# PCB_-_nrf52840.net
KiCad netlist of a schematic drawn in EAGLE
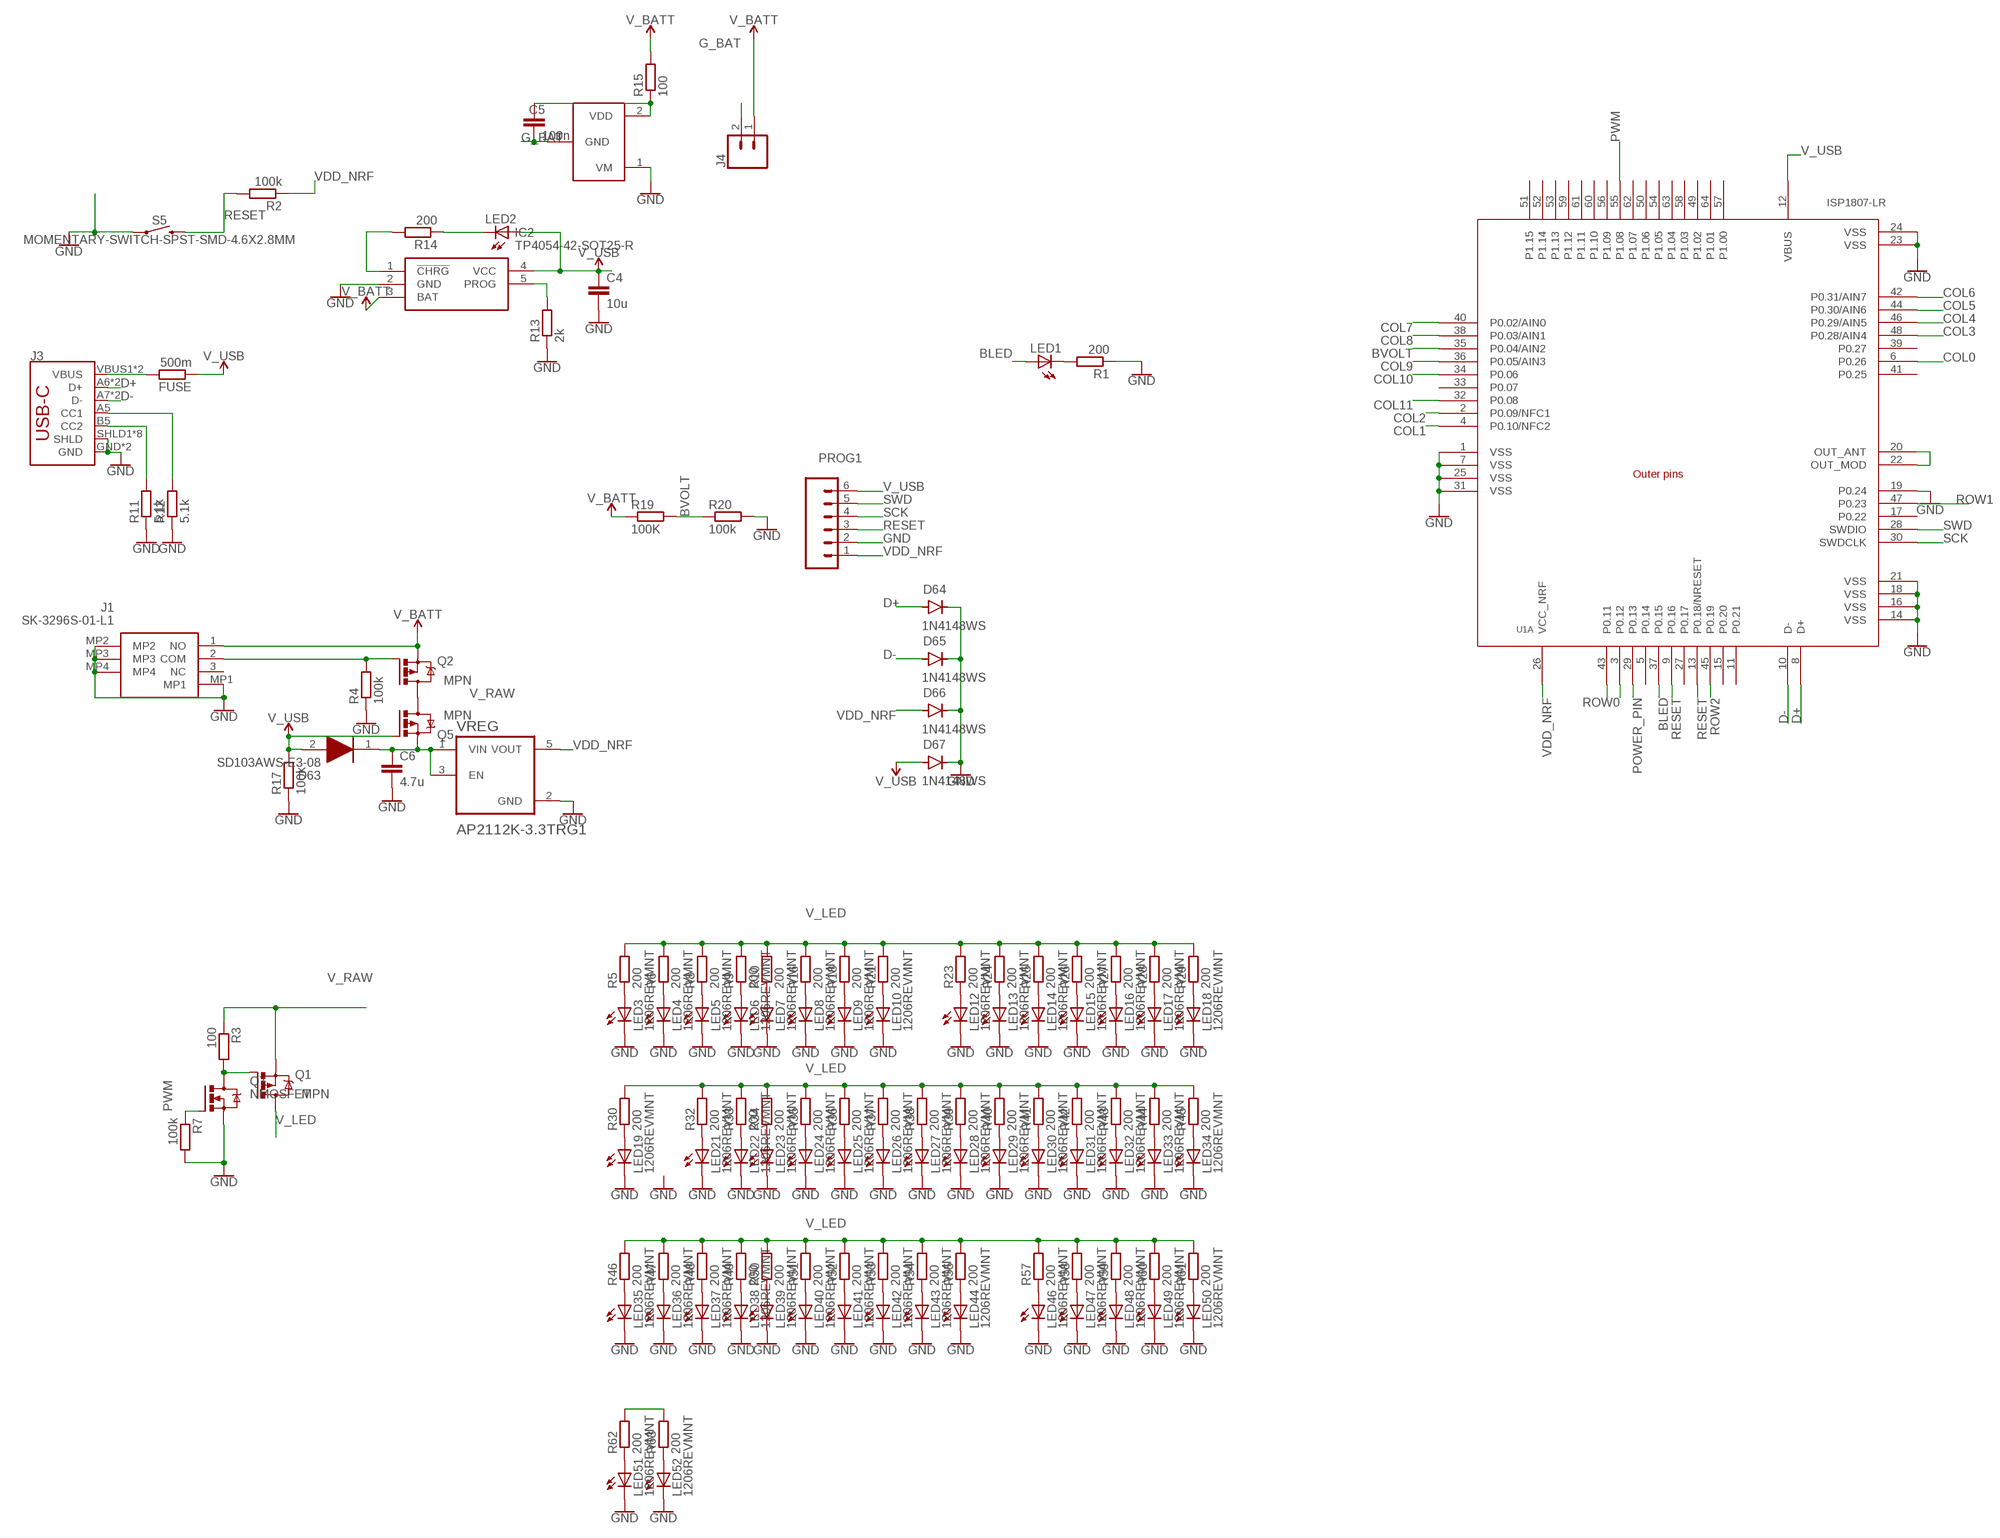
[diagram p0: schematic, sheet 1, part 1 of 2]
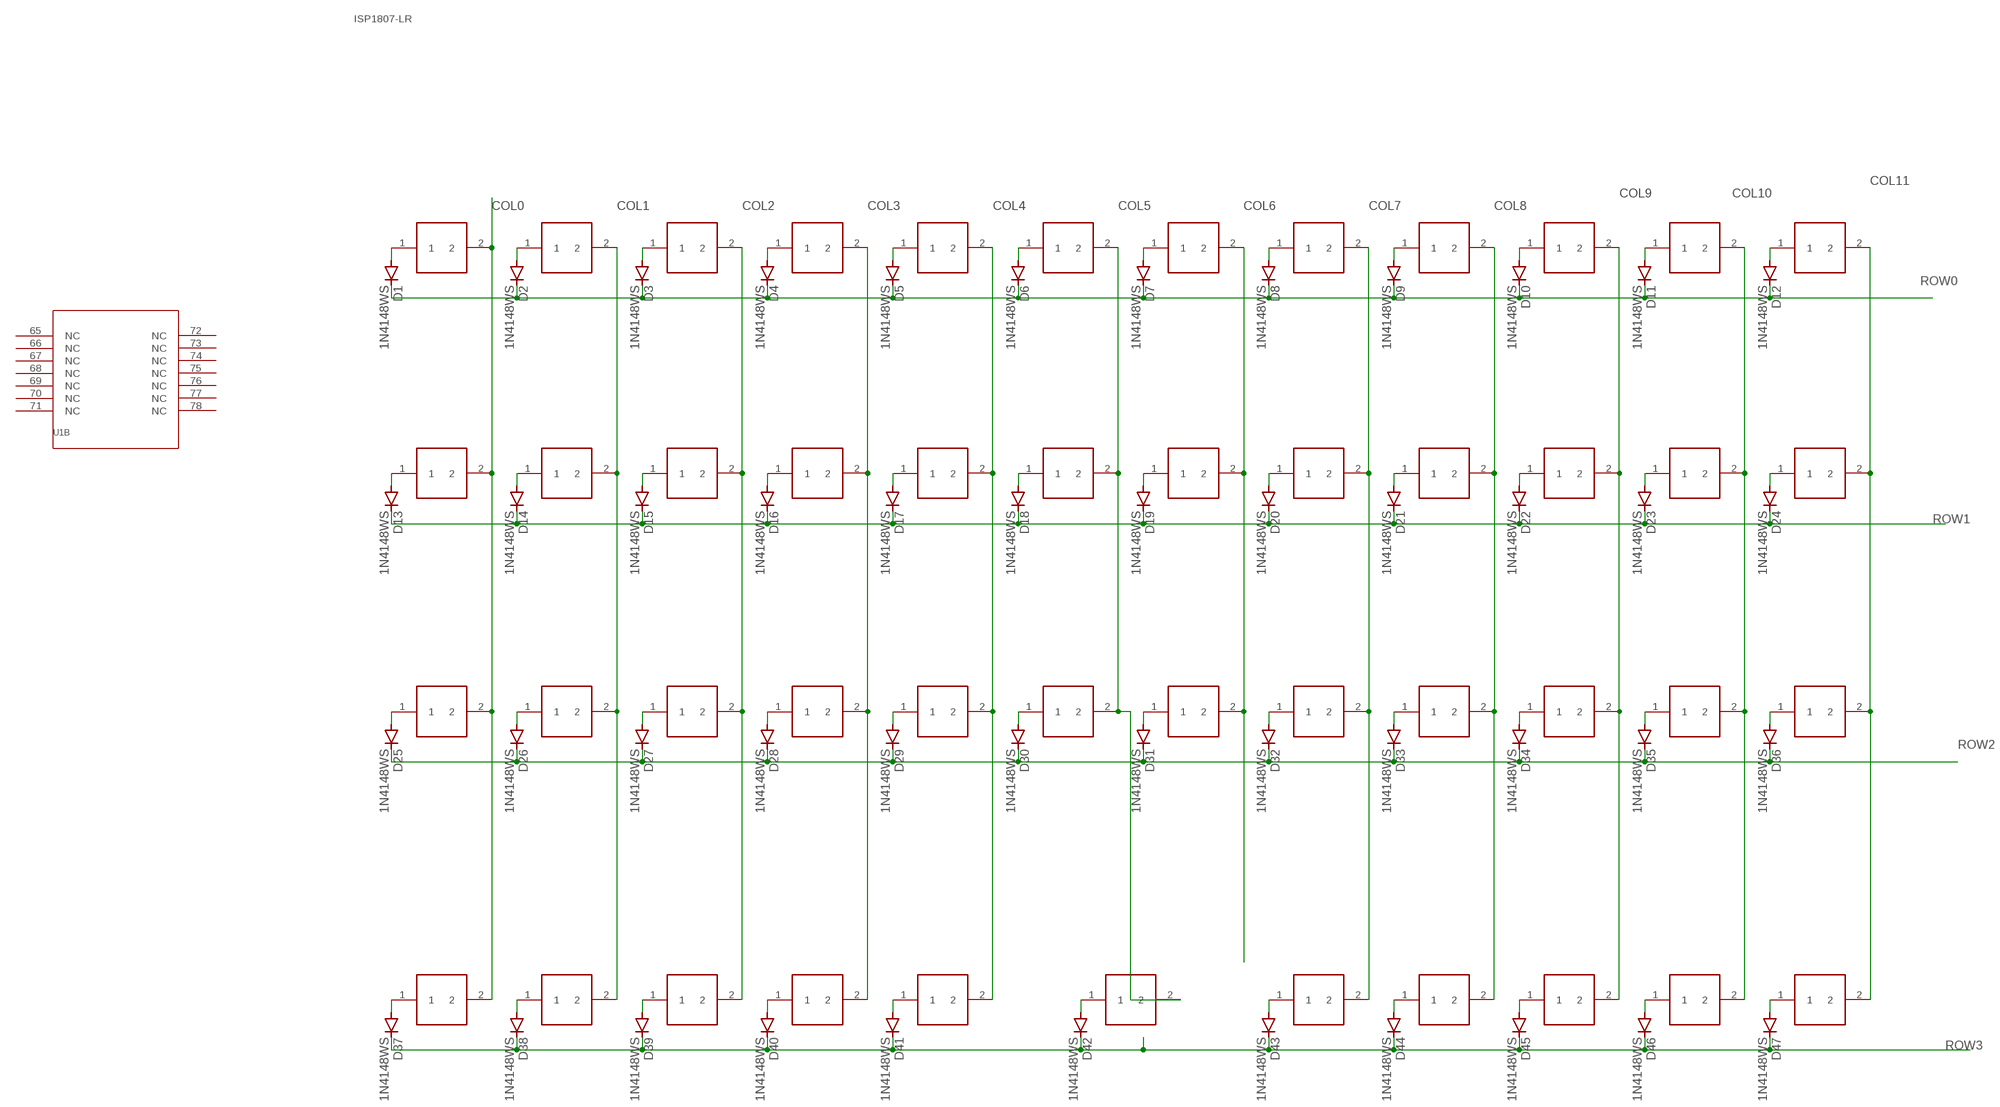
[diagram p1: schematic, sheet 1, part 2 of 2]

(export (version "E")
  (design (tool "Eeschema 10.0.6"))
  (components
    (comp (ref "5")
      (value "CHERRYLOWPRO")
      (footprint "eagle-import:CHERRY-LOWPRO")
      (libsource (lib "eagle-import") (part "CHERRYLOWPRO"))
    )
    (comp (ref "6")
      (value "CHERRYLOWPRO")
      (footprint "eagle-import:CHERRY-LOWPRO")
      (libsource (lib "eagle-import") (part "CHERRYLOWPRO"))
    )
    (comp (ref "7")
      (value "CHERRYLOWPRO")
      (footprint "eagle-import:CHERRY-LOWPRO")
      (libsource (lib "eagle-import") (part "CHERRYLOWPRO"))
    )
    (comp (ref "8")
      (value "CHERRYLOWPRO")
      (footprint "eagle-import:CHERRY-LOWPRO")
      (libsource (lib "eagle-import") (part "CHERRYLOWPRO"))
    )
    (comp (ref "12")
      (value "CHERRYLOWPRO")
      (footprint "eagle-import:CHERRY-LOWPRO")
      (libsource (lib "eagle-import") (part "CHERRYLOWPRO"))
    )
    (comp (ref "13")
      (value "CHERRYLOWPRO")
      (footprint "eagle-import:CHERRY-LOWPRO")
      (libsource (lib "eagle-import") (part "CHERRYLOWPRO"))
    )
    (comp (ref "14")
      (value "CHERRYLOWPRO")
      (footprint "eagle-import:CHERRY-LOWPRO")
      (libsource (lib "eagle-import") (part "CHERRYLOWPRO"))
    )
    (comp (ref "15")
      (value "CHERRYLOWPRO")
      (footprint "eagle-import:CHERRY-LOWPRO")
      (libsource (lib "eagle-import") (part "CHERRYLOWPRO"))
    )
    (comp (ref "16")
      (value "CHERRYLOWPRO")
      (footprint "eagle-import:CHERRY-LOWPRO")
      (libsource (lib "eagle-import") (part "CHERRYLOWPRO"))
    )
    (comp (ref "17")
      (value "CHERRYLOWPRO")
      (footprint "eagle-import:CHERRY-LOWPRO")
      (libsource (lib "eagle-import") (part "CHERRYLOWPRO"))
    )
    (comp (ref "18")
      (value "CHERRYLOWPRO")
      (footprint "eagle-import:CHERRY-LOWPRO")
      (libsource (lib "eagle-import") (part "CHERRYLOWPRO"))
    )
    (comp (ref "19")
      (value "CHERRYLOWPRO")
      (footprint "eagle-import:CHERRY-LOWPRO")
      (libsource (lib "eagle-import") (part "CHERRYLOWPRO"))
    )
    (comp (ref "21")
      (value "CHERRYLOWPRO")
      (footprint "eagle-import:CHERRY-LOWPRO")
      (libsource (lib "eagle-import") (part "CHERRYLOWPRO"))
    )
    (comp (ref "22")
      (value "CHERRYLOWPRO")
      (footprint "eagle-import:CHERRY-LOWPRO")
      (libsource (lib "eagle-import") (part "CHERRYLOWPRO"))
    )
    (comp (ref "23")
      (value "CHERRYLOWPRO")
      (footprint "eagle-import:CHERRY-LOWPRO")
      (libsource (lib "eagle-import") (part "CHERRYLOWPRO"))
    )
    (comp (ref "24")
      (value "CHERRYLOWPRO")
      (footprint "eagle-import:CHERRY-LOWPRO")
      (libsource (lib "eagle-import") (part "CHERRYLOWPRO"))
    )
    (comp (ref "25")
      (value "CHERRYLOWPRO")
      (footprint "eagle-import:CHERRY-LOWPRO")
      (libsource (lib "eagle-import") (part "CHERRYLOWPRO"))
    )
    (comp (ref "26")
      (value "CHERRYLOWPRO")
      (footprint "eagle-import:CHERRY-LOWPRO")
      (libsource (lib "eagle-import") (part "CHERRYLOWPRO"))
    )
    (comp (ref "27")
      (value "CHERRYLOWPRO")
      (footprint "eagle-import:CHERRY-LOWPRO")
      (libsource (lib "eagle-import") (part "CHERRYLOWPRO"))
    )
    (comp (ref "28")
      (value "CHERRYLOWPRO")
      (footprint "eagle-import:CHERRY-LOWPRO")
      (libsource (lib "eagle-import") (part "CHERRYLOWPRO"))
    )
    (comp (ref "29")
      (value "CHERRYLOWPRO")
      (footprint "eagle-import:CHERRY-LOWPRO")
      (libsource (lib "eagle-import") (part "CHERRYLOWPRO"))
    )
    (comp (ref "31")
      (value "CHERRYLOWPRO")
      (footprint "eagle-import:CHERRY-LOWPRO")
      (libsource (lib "eagle-import") (part "CHERRYLOWPRO"))
    )
    (comp (ref "32")
      (value "CHERRYLOWPRO")
      (footprint "eagle-import:CHERRY-LOWPRO")
      (libsource (lib "eagle-import") (part "CHERRYLOWPRO"))
    )
    (comp (ref "33")
      (value "CHERRYLOWPRO")
      (footprint "eagle-import:CHERRY-LOWPRO")
      (libsource (lib "eagle-import") (part "CHERRYLOWPRO"))
    )
    (comp (ref "34")
      (value "CHERRYLOWPRO")
      (footprint "eagle-import:CHERRY-LOWPRO")
      (libsource (lib "eagle-import") (part "CHERRYLOWPRO"))
    )
    (comp (ref "35")
      (value "CHERRYLOWPRO")
      (footprint "eagle-import:CHERRY-LOWPRO")
      (libsource (lib "eagle-import") (part "CHERRYLOWPRO"))
    )
    (comp (ref "36")
      (value "CHERRYLOWPRO")
      (footprint "eagle-import:CHERRY-LOWPRO")
      (libsource (lib "eagle-import") (part "CHERRYLOWPRO"))
    )
    (comp (ref "37")
      (value "CHERRYLOWPRO")
      (footprint "eagle-import:CHERRY-LOWPRO")
      (libsource (lib "eagle-import") (part "CHERRYLOWPRO"))
    )
    (comp (ref "38")
      (value "CHERRYLOWPRO")
      (footprint "eagle-import:CHERRY-LOWPRO")
      (libsource (lib "eagle-import") (part "CHERRYLOWPRO"))
    )
    (comp (ref "39")
      (value "CHERRYLOWPRO")
      (footprint "eagle-import:CHERRY-LOWPRO")
      (libsource (lib "eagle-import") (part "CHERRYLOWPRO"))
    )
    (comp (ref "42")
      (value "CHERRYLOWPRO")
      (footprint "eagle-import:CHERRY-LOWPRO")
      (libsource (lib "eagle-import") (part "CHERRYLOWPRO"))
    )
    (comp (ref "43")
      (value "CHERRYLOWPRO")
      (footprint "eagle-import:CHERRY-LOWPRO")
      (libsource (lib "eagle-import") (part "CHERRYLOWPRO"))
    )
    (comp (ref "44")
      (value "CHERRYLOWPRO")
      (footprint "eagle-import:CHERRY-LOWPRO")
      (libsource (lib "eagle-import") (part "CHERRYLOWPRO"))
    )
    (comp (ref "45")
      (value "CHERRYLOWPRO")
      (footprint "eagle-import:CHERRY-LOWPRO")
      (libsource (lib "eagle-import") (part "CHERRYLOWPRO"))
    )
    (comp (ref "46")
      (value "CHERRYLOWPRO")
      (footprint "eagle-import:CHERRY-LOWPRO")
      (libsource (lib "eagle-import") (part "CHERRYLOWPRO"))
    )
    (comp (ref "47")
      (value "CHERRYLOWPRO")
      (footprint "eagle-import:CHERRY-LOWPRO")
      (libsource (lib "eagle-import") (part "CHERRYLOWPRO"))
    )
    (comp (ref "48")
      (value "CHERRYLOWPRO")
      (footprint "eagle-import:CHERRY-LOWPRO")
      (libsource (lib "eagle-import") (part "CHERRYLOWPRO"))
    )
    (comp (ref "49")
      (value "CHERRYLOWPRO")
      (footprint "eagle-import:CHERRY-LOWPRO")
      (libsource (lib "eagle-import") (part "CHERRYLOWPRO"))
    )
    (comp (ref "110")
      (value "CHERRYLOWPRO")
      (footprint "eagle-import:CHERRY-LOWPRO")
      (libsource (lib "eagle-import") (part "CHERRYLOWPRO"))
    )
    (comp (ref "111")
      (value "CHERRYLOWPRO")
      (footprint "eagle-import:CHERRY-LOWPRO")
      (libsource (lib "eagle-import") (part "CHERRYLOWPRO"))
    )
    (comp (ref "210")
      (value "CHERRYLOWPRO")
      (footprint "eagle-import:CHERRY-LOWPRO")
      (libsource (lib "eagle-import") (part "CHERRYLOWPRO"))
    )
    (comp (ref "211")
      (value "CHERRYLOWPRO")
      (footprint "eagle-import:CHERRY-LOWPRO")
      (libsource (lib "eagle-import") (part "CHERRYLOWPRO"))
    )
    (comp (ref "212")
      (value "CHERRYLOWPRO")
      (footprint "eagle-import:CHERRY-LOWPRO")
      (libsource (lib "eagle-import") (part "CHERRYLOWPRO"))
    )
    (comp (ref "310")
      (value "CHERRYLOWPRO")
      (footprint "eagle-import:CHERRY-LOWPRO")
      (libsource (lib "eagle-import") (part "CHERRYLOWPRO"))
    )
    (comp (ref "311")
      (value "CHERRYLOWPRO")
      (footprint "eagle-import:CHERRY-LOWPRO")
      (libsource (lib "eagle-import") (part "CHERRYLOWPRO"))
    )
    (comp (ref "312")
      (value "CHERRYLOWPRO")
      (footprint "eagle-import:CHERRY-LOWPRO")
      (libsource (lib "eagle-import") (part "CHERRYLOWPRO"))
    )
    (comp (ref "410")
      (value "CHERRYLOWPRO")
      (footprint "eagle-import:CHERRY-LOWPRO")
      (libsource (lib "eagle-import") (part "CHERRYLOWPRO"))
    )
    (comp (ref "C4")
      (value "10u")
      (footprint "eagle-import:C0603")
      (libsource (lib "eagle-import") (part "resistor_348_C-EUC0603"))
    )
    (comp (ref "C5")
      (value "100n")
      (footprint "eagle-import:C0603")
      (libsource (lib "eagle-import") (part "resistor_348_C-EUC0603"))
    )
    (comp (ref "C6")
      (value "4.7u")
      (footprint "eagle-import:C0603")
      (libsource (lib "eagle-import") (part "C-EUC0603"))
    )
    (comp (ref "D1")
      (value "1N4148WS")
      (footprint "eagle-import:SOD-323")
      (fields
        (field (name "DIGIKEY_PART_NUMBER") "1N4148WSFSTR-ND")
        (field (name "MANUFACTURER") "Diodes Incorporated")
        (field (name "CREATED_BY") "PCBLayout.com")
      )
      (libsource (lib "eagle-import") (part "Volume_V1_32198814_1N4148WS"))
    )
    (comp (ref "D2")
      (value "1N4148WS")
      (footprint "eagle-import:SOD-323")
      (fields
        (field (name "DIGIKEY_PART_NUMBER") "1N4148WSFSTR-ND")
        (field (name "MANUFACTURER") "Diodes Incorporated")
        (field (name "CREATED_BY") "PCBLayout.com")
      )
      (libsource (lib "eagle-import") (part "Volume_V1_32198814_1N4148WS"))
    )
    (comp (ref "D3")
      (value "1N4148WS")
      (footprint "eagle-import:SOD-323")
      (fields
        (field (name "DIGIKEY_PART_NUMBER") "1N4148WSFSTR-ND")
        (field (name "MANUFACTURER") "Diodes Incorporated")
        (field (name "CREATED_BY") "PCBLayout.com")
      )
      (libsource (lib "eagle-import") (part "Volume_V1_32198814_1N4148WS"))
    )
    (comp (ref "D4")
      (value "1N4148WS")
      (footprint "eagle-import:SOD-323")
      (fields
        (field (name "DIGIKEY_PART_NUMBER") "1N4148WSFSTR-ND")
        (field (name "MANUFACTURER") "Diodes Incorporated")
        (field (name "CREATED_BY") "PCBLayout.com")
      )
      (libsource (lib "eagle-import") (part "Volume_V1_32198814_1N4148WS"))
    )
    (comp (ref "D5")
      (value "1N4148WS")
      (footprint "eagle-import:SOD-323")
      (fields
        (field (name "DIGIKEY_PART_NUMBER") "1N4148WSFSTR-ND")
        (field (name "MANUFACTURER") "Diodes Incorporated")
        (field (name "CREATED_BY") "PCBLayout.com")
      )
      (libsource (lib "eagle-import") (part "Volume_V1_32198814_1N4148WS"))
    )
    (comp (ref "D6")
      (value "1N4148WS")
      (footprint "eagle-import:SOD-323")
      (fields
        (field (name "DIGIKEY_PART_NUMBER") "1N4148WSFSTR-ND")
        (field (name "MANUFACTURER") "Diodes Incorporated")
        (field (name "CREATED_BY") "PCBLayout.com")
      )
      (libsource (lib "eagle-import") (part "Volume_V1_32198814_1N4148WS"))
    )
    (comp (ref "D7")
      (value "1N4148WS")
      (footprint "eagle-import:SOD-323")
      (fields
        (field (name "DIGIKEY_PART_NUMBER") "1N4148WSFSTR-ND")
        (field (name "MANUFACTURER") "Diodes Incorporated")
        (field (name "CREATED_BY") "PCBLayout.com")
      )
      (libsource (lib "eagle-import") (part "Volume_V1_32198814_1N4148WS"))
    )
    (comp (ref "D8")
      (value "1N4148WS")
      (footprint "eagle-import:SOD-323")
      (fields
        (field (name "DIGIKEY_PART_NUMBER") "1N4148WSFSTR-ND")
        (field (name "MANUFACTURER") "Diodes Incorporated")
        (field (name "CREATED_BY") "PCBLayout.com")
      )
      (libsource (lib "eagle-import") (part "Volume_V1_32198814_1N4148WS"))
    )
    (comp (ref "D9")
      (value "1N4148WS")
      (footprint "eagle-import:SOD-323")
      (fields
        (field (name "DIGIKEY_PART_NUMBER") "1N4148WSFSTR-ND")
        (field (name "MANUFACTURER") "Diodes Incorporated")
        (field (name "CREATED_BY") "PCBLayout.com")
      )
      (libsource (lib "eagle-import") (part "Volume_V1_32198814_1N4148WS"))
    )
    (comp (ref "D10")
      (value "1N4148WS")
      (footprint "eagle-import:SOD-323")
      (fields
        (field (name "DIGIKEY_PART_NUMBER") "1N4148WSFSTR-ND")
        (field (name "MANUFACTURER") "Diodes Incorporated")
        (field (name "CREATED_BY") "PCBLayout.com")
      )
      (libsource (lib "eagle-import") (part "Volume_V1_32198814_1N4148WS"))
    )
    (comp (ref "D11")
      (value "1N4148WS")
      (footprint "eagle-import:SOD-323")
      (fields
        (field (name "DIGIKEY_PART_NUMBER") "1N4148WSFSTR-ND")
        (field (name "MANUFACTURER") "Diodes Incorporated")
        (field (name "CREATED_BY") "PCBLayout.com")
      )
      (libsource (lib "eagle-import") (part "Volume_V1_32198814_1N4148WS"))
    )
    (comp (ref "D12")
      (value "1N4148WS")
      (footprint "eagle-import:SOD-323")
      (fields
        (field (name "DIGIKEY_PART_NUMBER") "1N4148WSFSTR-ND")
        (field (name "MANUFACTURER") "Diodes Incorporated")
        (field (name "CREATED_BY") "PCBLayout.com")
      )
      (libsource (lib "eagle-import") (part "Volume_V1_32198814_1N4148WS"))
    )
    (comp (ref "D13")
      (value "1N4148WS")
      (footprint "eagle-import:SOD-323")
      (fields
        (field (name "DIGIKEY_PART_NUMBER") "1N4148WSFSTR-ND")
        (field (name "MANUFACTURER") "Diodes Incorporated")
        (field (name "CREATED_BY") "PCBLayout.com")
      )
      (libsource (lib "eagle-import") (part "Volume_V1_32198814_1N4148WS"))
    )
    (comp (ref "D14")
      (value "1N4148WS")
      (footprint "eagle-import:SOD-323")
      (fields
        (field (name "DIGIKEY_PART_NUMBER") "1N4148WSFSTR-ND")
        (field (name "MANUFACTURER") "Diodes Incorporated")
        (field (name "CREATED_BY") "PCBLayout.com")
      )
      (libsource (lib "eagle-import") (part "Volume_V1_32198814_1N4148WS"))
    )
    (comp (ref "D15")
      (value "1N4148WS")
      (footprint "eagle-import:SOD-323")
      (fields
        (field (name "DIGIKEY_PART_NUMBER") "1N4148WSFSTR-ND")
        (field (name "MANUFACTURER") "Diodes Incorporated")
        (field (name "CREATED_BY") "PCBLayout.com")
      )
      (libsource (lib "eagle-import") (part "Volume_V1_32198814_1N4148WS"))
    )
    (comp (ref "D16")
      (value "1N4148WS")
      (footprint "eagle-import:SOD-323")
      (fields
        (field (name "DIGIKEY_PART_NUMBER") "1N4148WSFSTR-ND")
        (field (name "MANUFACTURER") "Diodes Incorporated")
        (field (name "CREATED_BY") "PCBLayout.com")
      )
      (libsource (lib "eagle-import") (part "Volume_V1_32198814_1N4148WS"))
    )
    (comp (ref "D17")
      (value "1N4148WS")
      (footprint "eagle-import:SOD-323")
      (fields
        (field (name "DIGIKEY_PART_NUMBER") "1N4148WSFSTR-ND")
        (field (name "MANUFACTURER") "Diodes Incorporated")
        (field (name "CREATED_BY") "PCBLayout.com")
      )
      (libsource (lib "eagle-import") (part "Volume_V1_32198814_1N4148WS"))
    )
    (comp (ref "D18")
      (value "1N4148WS")
      (footprint "eagle-import:SOD-323")
      (fields
        (field (name "DIGIKEY_PART_NUMBER") "1N4148WSFSTR-ND")
        (field (name "MANUFACTURER") "Diodes Incorporated")
        (field (name "CREATED_BY") "PCBLayout.com")
      )
      (libsource (lib "eagle-import") (part "Volume_V1_32198814_1N4148WS"))
    )
    (comp (ref "D19")
      (value "1N4148WS")
      (footprint "eagle-import:SOD-323")
      (fields
        (field (name "DIGIKEY_PART_NUMBER") "1N4148WSFSTR-ND")
        (field (name "MANUFACTURER") "Diodes Incorporated")
        (field (name "CREATED_BY") "PCBLayout.com")
      )
      (libsource (lib "eagle-import") (part "Volume_V1_32198814_1N4148WS"))
    )
    (comp (ref "D20")
      (value "1N4148WS")
      (footprint "eagle-import:SOD-323")
      (fields
        (field (name "DIGIKEY_PART_NUMBER") "1N4148WSFSTR-ND")
        (field (name "MANUFACTURER") "Diodes Incorporated")
        (field (name "CREATED_BY") "PCBLayout.com")
      )
      (libsource (lib "eagle-import") (part "Volume_V1_32198814_1N4148WS"))
    )
    (comp (ref "D21")
      (value "1N4148WS")
      (footprint "eagle-import:SOD-323")
      (fields
        (field (name "DIGIKEY_PART_NUMBER") "1N4148WSFSTR-ND")
        (field (name "MANUFACTURER") "Diodes Incorporated")
        (field (name "CREATED_BY") "PCBLayout.com")
      )
      (libsource (lib "eagle-import") (part "Volume_V1_32198814_1N4148WS"))
    )
    (comp (ref "D22")
      (value "1N4148WS")
      (footprint "eagle-import:SOD-323")
      (fields
        (field (name "DIGIKEY_PART_NUMBER") "1N4148WSFSTR-ND")
        (field (name "MANUFACTURER") "Diodes Incorporated")
        (field (name "CREATED_BY") "PCBLayout.com")
      )
      (libsource (lib "eagle-import") (part "Volume_V1_32198814_1N4148WS"))
    )
    (comp (ref "D23")
      (value "1N4148WS")
      (footprint "eagle-import:SOD-323")
      (fields
        (field (name "DIGIKEY_PART_NUMBER") "1N4148WSFSTR-ND")
        (field (name "MANUFACTURER") "Diodes Incorporated")
        (field (name "CREATED_BY") "PCBLayout.com")
      )
      (libsource (lib "eagle-import") (part "Volume_V1_32198814_1N4148WS"))
    )
    (comp (ref "D24")
      (value "1N4148WS")
      (footprint "eagle-import:SOD-323")
      (fields
        (field (name "DIGIKEY_PART_NUMBER") "1N4148WSFSTR-ND")
        (field (name "MANUFACTURER") "Diodes Incorporated")
        (field (name "CREATED_BY") "PCBLayout.com")
      )
      (libsource (lib "eagle-import") (part "Volume_V1_32198814_1N4148WS"))
    )
    (comp (ref "D25")
      (value "1N4148WS")
      (footprint "eagle-import:SOD-323")
      (fields
        (field (name "DIGIKEY_PART_NUMBER") "1N4148WSFSTR-ND")
        (field (name "MANUFACTURER") "Diodes Incorporated")
        (field (name "CREATED_BY") "PCBLayout.com")
      )
      (libsource (lib "eagle-import") (part "Volume_V1_32198814_1N4148WS"))
    )
    (comp (ref "D26")
      (value "1N4148WS")
      (footprint "eagle-import:SOD-323")
      (fields
        (field (name "DIGIKEY_PART_NUMBER") "1N4148WSFSTR-ND")
        (field (name "MANUFACTURER") "Diodes Incorporated")
        (field (name "CREATED_BY") "PCBLayout.com")
      )
      (libsource (lib "eagle-import") (part "Volume_V1_32198814_1N4148WS"))
    )
    (comp (ref "D27")
      (value "1N4148WS")
      (footprint "eagle-import:SOD-323")
      (fields
        (field (name "DIGIKEY_PART_NUMBER") "1N4148WSFSTR-ND")
        (field (name "MANUFACTURER") "Diodes Incorporated")
        (field (name "CREATED_BY") "PCBLayout.com")
      )
      (libsource (lib "eagle-import") (part "Volume_V1_32198814_1N4148WS"))
    )
    (comp (ref "D28")
      (value "1N4148WS")
      (footprint "eagle-import:SOD-323")
      (fields
        (field (name "DIGIKEY_PART_NUMBER") "1N4148WSFSTR-ND")
        (field (name "MANUFACTURER") "Diodes Incorporated")
        (field (name "CREATED_BY") "PCBLayout.com")
      )
      (libsource (lib "eagle-import") (part "Volume_V1_32198814_1N4148WS"))
    )
    (comp (ref "D29")
      (value "1N4148WS")
      (footprint "eagle-import:SOD-323")
      (fields
        (field (name "DIGIKEY_PART_NUMBER") "1N4148WSFSTR-ND")
        (field (name "MANUFACTURER") "Diodes Incorporated")
        (field (name "CREATED_BY") "PCBLayout.com")
      )
      (libsource (lib "eagle-import") (part "Volume_V1_32198814_1N4148WS"))
    )
    (comp (ref "D30")
      (value "1N4148WS")
      (footprint "eagle-import:SOD-323")
      (fields
        (field (name "DIGIKEY_PART_NUMBER") "1N4148WSFSTR-ND")
        (field (name "MANUFACTURER") "Diodes Incorporated")
        (field (name "CREATED_BY") "PCBLayout.com")
      )
      (libsource (lib "eagle-import") (part "Volume_V1_32198814_1N4148WS"))
    )
    (comp (ref "D31")
      (value "1N4148WS")
      (footprint "eagle-import:SOD-323")
      (fields
        (field (name "DIGIKEY_PART_NUMBER") "1N4148WSFSTR-ND")
        (field (name "MANUFACTURER") "Diodes Incorporated")
        (field (name "CREATED_BY") "PCBLayout.com")
      )
      (libsource (lib "eagle-import") (part "Volume_V1_32198814_1N4148WS"))
    )
    (comp (ref "D32")
      (value "1N4148WS")
      (footprint "eagle-import:SOD-323")
      (fields
        (field (name "DIGIKEY_PART_NUMBER") "1N4148WSFSTR-ND")
        (field (name "MANUFACTURER") "Diodes Incorporated")
        (field (name "CREATED_BY") "PCBLayout.com")
      )
      (libsource (lib "eagle-import") (part "Volume_V1_32198814_1N4148WS"))
    )
    (comp (ref "D33")
      (value "1N4148WS")
      (footprint "eagle-import:SOD-323")
      (fields
        (field (name "DIGIKEY_PART_NUMBER") "1N4148WSFSTR-ND")
        (field (name "MANUFACTURER") "Diodes Incorporated")
        (field (name "CREATED_BY") "PCBLayout.com")
      )
      (libsource (lib "eagle-import") (part "Volume_V1_32198814_1N4148WS"))
    )
    (comp (ref "D34")
      (value "1N4148WS")
      (footprint "eagle-import:SOD-323")
      (fields
        (field (name "DIGIKEY_PART_NUMBER") "1N4148WSFSTR-ND")
        (field (name "MANUFACTURER") "Diodes Incorporated")
        (field (name "CREATED_BY") "PCBLayout.com")
      )
      (libsource (lib "eagle-import") (part "Volume_V1_32198814_1N4148WS"))
    )
    (comp (ref "D35")
      (value "1N4148WS")
      (footprint "eagle-import:SOD-323")
      (fields
        (field (name "DIGIKEY_PART_NUMBER") "1N4148WSFSTR-ND")
        (field (name "MANUFACTURER") "Diodes Incorporated")
        (field (name "CREATED_BY") "PCBLayout.com")
      )
      (libsource (lib "eagle-import") (part "Volume_V1_32198814_1N4148WS"))
    )
    (comp (ref "D36")
      (value "1N4148WS")
      (footprint "eagle-import:SOD-323")
      (fields
        (field (name "DIGIKEY_PART_NUMBER") "1N4148WSFSTR-ND")
        (field (name "MANUFACTURER") "Diodes Incorporated")
        (field (name "CREATED_BY") "PCBLayout.com")
      )
      (libsource (lib "eagle-import") (part "Volume_V1_32198814_1N4148WS"))
    )
    (comp (ref "D37")
      (value "1N4148WS")
      (footprint "eagle-import:SOD-323")
      (fields
        (field (name "DIGIKEY_PART_NUMBER") "1N4148WSFSTR-ND")
        (field (name "MANUFACTURER") "Diodes Incorporated")
        (field (name "CREATED_BY") "PCBLayout.com")
      )
      (libsource (lib "eagle-import") (part "Volume_V1_32198814_1N4148WS"))
    )
    (comp (ref "D38")
      (value "1N4148WS")
      (footprint "eagle-import:SOD-323")
      (fields
        (field (name "DIGIKEY_PART_NUMBER") "1N4148WSFSTR-ND")
        (field (name "MANUFACTURER") "Diodes Incorporated")
        (field (name "CREATED_BY") "PCBLayout.com")
      )
      (libsource (lib "eagle-import") (part "Volume_V1_32198814_1N4148WS"))
    )
    (comp (ref "D39")
      (value "1N4148WS")
      (footprint "eagle-import:SOD-323")
      (fields
        (field (name "DIGIKEY_PART_NUMBER") "1N4148WSFSTR-ND")
        (field (name "MANUFACTURER") "Diodes Incorporated")
        (field (name "CREATED_BY") "PCBLayout.com")
      )
      (libsource (lib "eagle-import") (part "Volume_V1_32198814_1N4148WS"))
    )
    (comp (ref "D40")
      (value "1N4148WS")
      (footprint "eagle-import:SOD-323")
      (fields
        (field (name "DIGIKEY_PART_NUMBER") "1N4148WSFSTR-ND")
        (field (name "MANUFACTURER") "Diodes Incorporated")
        (field (name "CREATED_BY") "PCBLayout.com")
      )
      (libsource (lib "eagle-import") (part "Volume_V1_32198814_1N4148WS"))
    )
    (comp (ref "D41")
      (value "1N4148WS")
      (footprint "eagle-import:SOD-323")
      (fields
        (field (name "DIGIKEY_PART_NUMBER") "1N4148WSFSTR-ND")
        (field (name "MANUFACTURER") "Diodes Incorporated")
        (field (name "CREATED_BY") "PCBLayout.com")
      )
      (libsource (lib "eagle-import") (part "Volume_V1_32198814_1N4148WS"))
    )
    (comp (ref "D42")
      (value "1N4148WS")
      (footprint "eagle-import:SOD-323")
      (fields
        (field (name "DIGIKEY_PART_NUMBER") "1N4148WSFSTR-ND")
        (field (name "MANUFACTURER") "Diodes Incorporated")
        (field (name "CREATED_BY") "PCBLayout.com")
      )
      (libsource (lib "eagle-import") (part "Volume_V1_32198814_1N4148WS"))
    )
    (comp (ref "D43")
      (value "1N4148WS")
      (footprint "eagle-import:SOD-323")
      (fields
        (field (name "DIGIKEY_PART_NUMBER") "1N4148WSFSTR-ND")
        (field (name "MANUFACTURER") "Diodes Incorporated")
        (field (name "CREATED_BY") "PCBLayout.com")
      )
      (libsource (lib "eagle-import") (part "Volume_V1_32198814_1N4148WS"))
    )
    (comp (ref "D44")
      (value "1N4148WS")
      (footprint "eagle-import:SOD-323")
      (fields
        (field (name "DIGIKEY_PART_NUMBER") "1N4148WSFSTR-ND")
        (field (name "MANUFACTURER") "Diodes Incorporated")
        (field (name "CREATED_BY") "PCBLayout.com")
      )
      (libsource (lib "eagle-import") (part "Volume_V1_32198814_1N4148WS"))
    )
    (comp (ref "D45")
      (value "1N4148WS")
      (footprint "eagle-import:SOD-323")
      (fields
        (field (name "DIGIKEY_PART_NUMBER") "1N4148WSFSTR-ND")
        (field (name "MANUFACTURER") "Diodes Incorporated")
        (field (name "CREATED_BY") "PCBLayout.com")
      )
      (libsource (lib "eagle-import") (part "Volume_V1_32198814_1N4148WS"))
    )
    (comp (ref "D46")
      (value "1N4148WS")
      (footprint "eagle-import:SOD-323")
      (fields
        (field (name "DIGIKEY_PART_NUMBER") "1N4148WSFSTR-ND")
        (field (name "MANUFACTURER") "Diodes Incorporated")
        (field (name "CREATED_BY") "PCBLayout.com")
      )
      (libsource (lib "eagle-import") (part "Volume_V1_32198814_1N4148WS"))
    )
    (comp (ref "D47")
      (value "1N4148WS")
      (footprint "eagle-import:SOD-323")
      (fields
        (field (name "DIGIKEY_PART_NUMBER") "1N4148WSFSTR-ND")
        (field (name "MANUFACTURER") "Diodes Incorporated")
        (field (name "CREATED_BY") "PCBLayout.com")
      )
      (libsource (lib "eagle-import") (part "Volume_V1_32198814_1N4148WS"))
    )
    (comp (ref "D63")
      (value "SD103AWS-E3-08")
      (footprint "eagle-import:SOD2713X115N")
      (fields (field (name "MOUSER_PART_NUMBER") "78-SD103AWS-E3-08"))
      (libsource (lib "eagle-import") (part "SD103AWS-E3-08"))
    )
    (comp (ref "D64")
      (value "1N4148WS")
      (footprint "eagle-import:SOD-323")
      (fields
        (field (name "DIGIKEY_PART_NUMBER") "1N4148WSFSTR-ND")
        (field (name "MANUFACTURER") "Diodes Incorporated")
        (field (name "CREATED_BY") "PCBLayout.com")
      )
      (libsource (lib "eagle-import") (part "1N4148WS"))
    )
    (comp (ref "D65")
      (value "1N4148WS")
      (footprint "eagle-import:SOD-323")
      (fields
        (field (name "DIGIKEY_PART_NUMBER") "1N4148WSFSTR-ND")
        (field (name "MANUFACTURER") "Diodes Incorporated")
        (field (name "CREATED_BY") "PCBLayout.com")
      )
      (libsource (lib "eagle-import") (part "1N4148WS"))
    )
    (comp (ref "D66")
      (value "1N4148WS")
      (footprint "eagle-import:SOD-323")
      (fields
        (field (name "DIGIKEY_PART_NUMBER") "1N4148WSFSTR-ND")
        (field (name "MANUFACTURER") "Diodes Incorporated")
        (field (name "CREATED_BY") "PCBLayout.com")
      )
      (libsource (lib "eagle-import") (part "1N4148WS"))
    )
    (comp (ref "D67")
      (value "1N4148WS")
      (footprint "eagle-import:SOD-323")
      (fields
        (field (name "DIGIKEY_PART_NUMBER") "1N4148WSFSTR-ND")
        (field (name "MANUFACTURER") "Diodes Incorporated")
        (field (name "CREATED_BY") "PCBLayout.com")
      )
      (libsource (lib "eagle-import") (part "1N4148WS"))
    )
    (comp (ref "FUSE")
      (value "500m")
      (footprint "eagle-import:R0603")
      (libsource (lib "eagle-import") (part "rcl_334_R-EU_R0603"))
    )
    (comp (ref "IC1")
      (value "XB3303ASOT23")
      (footprint "eagle-import:SOT23-3")
      (libsource (lib "eagle-import") (part "XB3303ASOT23"))
    )
    (comp (ref "IC2")
      (value "TP4054-42-SOT25-R")
      (footprint "eagle-import:SOT95P280X100-5N")
      (libsource (lib "eagle-import") (part "TP4054-42-SOT25-R"))
    )
    (comp (ref "J1")
      (value "SK-3296S-01-L1")
      (footprint "eagle-import:SK3296S01L1")
      (libsource (lib "eagle-import") (part "SK-3296S-01-L1"))
    )
    (comp (ref "J3")
      (value "SPARKFUN-CONNECTORS_USB_C16PIN")
      (footprint "eagle-import:SPARKFUN-CONNECTORS_USB-C-16P")
      (libsource (lib "eagle-import") (part "SPARKFUN-CONNECTORS_USB_C16PIN"))
    )
    (comp (ref "J4")
      (value "CONN_02")
      (footprint "eagle-import:1X02")
      (libsource (lib "eagle-import") (part "CONN_02"))
    )
    (comp (ref "LED1")
      (value "LEDCHIPLED_0805")
      (footprint "eagle-import:CHIPLED_0805")
      (libsource (lib "eagle-import") (part "LEDCHIPLED_0805"))
    )
    (comp (ref "LED2")
      (value "LEDCHIPLED_0805")
      (footprint "eagle-import:CHIPLED_0805")
      (libsource (lib "eagle-import") (part "LEDCHIPLED_0805"))
    )
    (comp (ref "LED3")
      (value "1206REVMNT")
      (footprint "eagle-import:1206REVMNT")
      (libsource (lib "eagle-import") (part "1206REVMNT"))
    )
    (comp (ref "LED4")
      (value "1206REVMNT")
      (footprint "eagle-import:1206REVMNT")
      (libsource (lib "eagle-import") (part "1206REVMNT"))
    )
    (comp (ref "LED5")
      (value "1206REVMNT")
      (footprint "eagle-import:1206REVMNT")
      (libsource (lib "eagle-import") (part "1206REVMNT"))
    )
    (comp (ref "LED6")
      (value "1206REVMNT")
      (footprint "eagle-import:1206REVMNT")
      (libsource (lib "eagle-import") (part "1206REVMNT"))
    )
    (comp (ref "LED7")
      (value "1206REVMNT")
      (footprint "eagle-import:1206REVMNT")
      (libsource (lib "eagle-import") (part "1206REVMNT"))
    )
    (comp (ref "LED8")
      (value "1206REVMNT")
      (footprint "eagle-import:1206REVMNT")
      (libsource (lib "eagle-import") (part "1206REVMNT"))
    )
    (comp (ref "LED9")
      (value "1206REVMNT")
      (footprint "eagle-import:1206REVMNT")
      (libsource (lib "eagle-import") (part "1206REVMNT"))
    )
    (comp (ref "LED10")
      (value "1206REVMNT")
      (footprint "eagle-import:1206REVMNT")
      (libsource (lib "eagle-import") (part "1206REVMNT"))
    )
    (comp (ref "LED12")
      (value "1206REVMNT")
      (footprint "eagle-import:1206REVMNT")
      (libsource (lib "eagle-import") (part "1206REVMNT"))
    )
    (comp (ref "LED13")
      (value "1206REVMNT")
      (footprint "eagle-import:1206REVMNT")
      (libsource (lib "eagle-import") (part "1206REVMNT"))
    )
    (comp (ref "LED14")
      (value "1206REVMNT")
      (footprint "eagle-import:1206REVMNT")
      (libsource (lib "eagle-import") (part "1206REVMNT"))
    )
    (comp (ref "LED15")
      (value "1206REVMNT")
      (footprint "eagle-import:1206REVMNT")
      (libsource (lib "eagle-import") (part "1206REVMNT"))
    )
    (comp (ref "LED16")
      (value "1206REVMNT")
      (footprint "eagle-import:1206REVMNT")
      (libsource (lib "eagle-import") (part "1206REVMNT"))
    )
    (comp (ref "LED17")
      (value "1206REVMNT")
      (footprint "eagle-import:1206REVMNT")
      (libsource (lib "eagle-import") (part "1206REVMNT"))
    )
    (comp (ref "LED18")
      (value "1206REVMNT")
      (footprint "eagle-import:1206REVMNT")
      (libsource (lib "eagle-import") (part "1206REVMNT"))
    )
    (comp (ref "LED19")
      (value "1206REVMNT")
      (footprint "eagle-import:1206REVMNT")
      (libsource (lib "eagle-import") (part "1206REVMNT"))
    )
    (comp (ref "LED21")
      (value "1206REVMNT")
      (footprint "eagle-import:1206REVMNT")
      (libsource (lib "eagle-import") (part "1206REVMNT"))
    )
    (comp (ref "LED22")
      (value "1206REVMNT")
      (footprint "eagle-import:1206REVMNT")
      (libsource (lib "eagle-import") (part "1206REVMNT"))
    )
    (comp (ref "LED23")
      (value "1206REVMNT")
      (footprint "eagle-import:1206REVMNT")
      (libsource (lib "eagle-import") (part "1206REVMNT"))
    )
    (comp (ref "LED24")
      (value "1206REVMNT")
      (footprint "eagle-import:1206REVMNT")
      (libsource (lib "eagle-import") (part "1206REVMNT"))
    )
    (comp (ref "LED25")
      (value "1206REVMNT")
      (footprint "eagle-import:1206REVMNT")
      (libsource (lib "eagle-import") (part "1206REVMNT"))
    )
    (comp (ref "LED26")
      (value "1206REVMNT")
      (footprint "eagle-import:1206REVMNT")
      (libsource (lib "eagle-import") (part "1206REVMNT"))
    )
    (comp (ref "LED27")
      (value "1206REVMNT")
      (footprint "eagle-import:1206REVMNT")
      (libsource (lib "eagle-import") (part "1206REVMNT"))
    )
    (comp (ref "LED28")
      (value "1206REVMNT")
      (footprint "eagle-import:1206REVMNT")
      (libsource (lib "eagle-import") (part "1206REVMNT"))
    )
    (comp (ref "LED29")
      (value "1206REVMNT")
      (footprint "eagle-import:1206REVMNT")
      (libsource (lib "eagle-import") (part "1206REVMNT"))
    )
    (comp (ref "LED30")
      (value "1206REVMNT")
      (footprint "eagle-import:1206REVMNT")
      (libsource (lib "eagle-import") (part "1206REVMNT"))
    )
    (comp (ref "LED31")
      (value "1206REVMNT")
      (footprint "eagle-import:1206REVMNT")
      (libsource (lib "eagle-import") (part "1206REVMNT"))
    )
    (comp (ref "LED32")
      (value "1206REVMNT")
      (footprint "eagle-import:1206REVMNT")
      (libsource (lib "eagle-import") (part "1206REVMNT"))
    )
    (comp (ref "LED33")
      (value "1206REVMNT")
      (footprint "eagle-import:1206REVMNT")
      (libsource (lib "eagle-import") (part "1206REVMNT"))
    )
    (comp (ref "LED34")
      (value "1206REVMNT")
      (footprint "eagle-import:1206REVMNT")
      (libsource (lib "eagle-import") (part "1206REVMNT"))
    )
    (comp (ref "LED35")
      (value "1206REVMNT")
      (footprint "eagle-import:1206REVMNT")
      (libsource (lib "eagle-import") (part "1206REVMNT"))
    )
    (comp (ref "LED36")
      (value "1206REVMNT")
      (footprint "eagle-import:1206REVMNT")
      (libsource (lib "eagle-import") (part "1206REVMNT"))
    )
    (comp (ref "LED37")
      (value "1206REVMNT")
      (footprint "eagle-import:1206REVMNT")
      (libsource (lib "eagle-import") (part "1206REVMNT"))
    )
    (comp (ref "LED38")
      (value "1206REVMNT")
      (footprint "eagle-import:1206REVMNT")
      (libsource (lib "eagle-import") (part "1206REVMNT"))
    )
    (comp (ref "LED39")
      (value "1206REVMNT")
      (footprint "eagle-import:1206REVMNT")
      (libsource (lib "eagle-import") (part "1206REVMNT"))
    )
    (comp (ref "LED40")
      (value "1206REVMNT")
      (footprint "eagle-import:1206REVMNT")
      (libsource (lib "eagle-import") (part "1206REVMNT"))
    )
    (comp (ref "LED41")
      (value "1206REVMNT")
      (footprint "eagle-import:1206REVMNT")
      (libsource (lib "eagle-import") (part "1206REVMNT"))
    )
    (comp (ref "LED42")
      (value "1206REVMNT")
      (footprint "eagle-import:1206REVMNT")
      (libsource (lib "eagle-import") (part "1206REVMNT"))
    )
    (comp (ref "LED43")
      (value "1206REVMNT")
      (footprint "eagle-import:1206REVMNT")
      (libsource (lib "eagle-import") (part "1206REVMNT"))
    )
    (comp (ref "LED44")
      (value "1206REVMNT")
      (footprint "eagle-import:1206REVMNT")
      (libsource (lib "eagle-import") (part "1206REVMNT"))
    )
    (comp (ref "LED46")
      (value "1206REVMNT")
      (footprint "eagle-import:1206REVMNT")
      (libsource (lib "eagle-import") (part "1206REVMNT"))
    )
    (comp (ref "LED47")
      (value "1206REVMNT")
      (footprint "eagle-import:1206REVMNT")
      (libsource (lib "eagle-import") (part "1206REVMNT"))
    )
    (comp (ref "LED48")
      (value "1206REVMNT")
      (footprint "eagle-import:1206REVMNT")
      (libsource (lib "eagle-import") (part "1206REVMNT"))
    )
    (comp (ref "LED49")
      (value "1206REVMNT")
      (footprint "eagle-import:1206REVMNT")
      (libsource (lib "eagle-import") (part "1206REVMNT"))
    )
    (comp (ref "LED50")
      (value "1206REVMNT")
      (footprint "eagle-import:1206REVMNT")
      (libsource (lib "eagle-import") (part "1206REVMNT"))
    )
    (comp (ref "LED51")
      (value "1206REVMNT")
      (footprint "eagle-import:1206REVMNT")
      (libsource (lib "eagle-import") (part "1206REVMNT"))
    )
    (comp (ref "LED52")
      (value "1206REVMNT")
      (footprint "eagle-import:1206REVMNT")
      (libsource (lib "eagle-import") (part "1206REVMNT"))
    )
    (comp (ref "PROG1")
      (value "CONN_061.27MM")
      (footprint "eagle-import:1X06_1.27MM")
      (libsource (lib "eagle-import") (part "CONN_061.27MM"))
    )
    (comp (ref "Q1")
      (value "PMOSFET")
      (footprint "eagle-import:SOT23")
      (fields (field (name "MPN") "SL2301S"))
      (libsource (lib "eagle-import") (part "PMOSFETSOT23_"))
    )
    (comp (ref "Q2")
      (value "PMOSFET")
      (footprint "eagle-import:SOT23")
      (fields (field (name "MPN") "SL2301S"))
      (libsource (lib "eagle-import") (part "PMOSFETSOT23_"))
    )
    (comp (ref "Q5")
      (value "PMOSFET")
      (footprint "eagle-import:SOT23")
      (fields (field (name "MPN") "SL2301S"))
      (libsource (lib "eagle-import") (part "PMOSFETSOT23_"))
    )
    (comp (ref "Q7")
      (value "NMOSFET")
      (footprint "eagle-import:SOT23")
      (libsource (lib "eagle-import") (part "NMOSFETSOT23"))
    )
    (comp (ref "R1")
      (value "200")
      (footprint "eagle-import:R0603")
      (libsource (lib "eagle-import") (part "rcl_334_R-EU_R0603"))
    )
    (comp (ref "R2")
      (value "100k")
      (footprint "eagle-import:R0603")
      (libsource (lib "eagle-import") (part "rcl_334_R-EU_R0603"))
    )
    (comp (ref "R3")
      (value "100")
      (footprint "eagle-import:R0603")
      (libsource (lib "eagle-import") (part "R-EU_R0603"))
    )
    (comp (ref "R4")
      (value "100k")
      (footprint "eagle-import:R0603")
      (libsource (lib "eagle-import") (part "R-EU_R0603"))
    )
    (comp (ref "R5")
      (value "200")
      (footprint "eagle-import:R0603")
      (libsource (lib "eagle-import") (part "R-EU_R0603"))
    )
    (comp (ref "R6")
      (value "200")
      (footprint "eagle-import:R0603")
      (libsource (lib "eagle-import") (part "R-EU_R0603"))
    )
    (comp (ref "R7")
      (value "100k")
      (footprint "eagle-import:R0603")
      (libsource (lib "eagle-import") (part "R-EU_R0603"))
    )
    (comp (ref "R8")
      (value "200")
      (footprint "eagle-import:R0603")
      (libsource (lib "eagle-import") (part "R-EU_R0603"))
    )
    (comp (ref "R9")
      (value "200")
      (footprint "eagle-import:R0603")
      (libsource (lib "eagle-import") (part "R-EU_R0603"))
    )
    (comp (ref "R10")
      (value "200")
      (footprint "eagle-import:R0603")
      (libsource (lib "eagle-import") (part "R-EU_R0603"))
    )
    (comp (ref "R11")
      (value "5.1k")
      (footprint "eagle-import:R0603")
      (libsource (lib "eagle-import") (part "rcl_334_R-EU_R0603"))
    )
    (comp (ref "R12")
      (value "5.1k")
      (footprint "eagle-import:R0603")
      (libsource (lib "eagle-import") (part "rcl_334_R-EU_R0603"))
    )
    (comp (ref "R13")
      (value "2k")
      (footprint "eagle-import:R0603")
      (libsource (lib "eagle-import") (part "rcl_334_R-EU_R0603"))
    )
    (comp (ref "R14")
      (value "200")
      (footprint "eagle-import:R0603")
      (libsource (lib "eagle-import") (part "rcl_334_R-EU_R0603"))
    )
    (comp (ref "R15")
      (value "100")
      (footprint "eagle-import:R0603")
      (libsource (lib "eagle-import") (part "rcl_334_R-EU_R0603"))
    )
    (comp (ref "R16")
      (value "200")
      (footprint "eagle-import:R0603")
      (libsource (lib "eagle-import") (part "R-EU_R0603"))
    )
    (comp (ref "R17")
      (value "100k")
      (footprint "eagle-import:R0603")
      (libsource (lib "eagle-import") (part "R-EU_R0603"))
    )
    (comp (ref "R18")
      (value "200")
      (footprint "eagle-import:R0603")
      (libsource (lib "eagle-import") (part "R-EU_R0603"))
    )
    (comp (ref "R19")
      (value "100K")
      (footprint "eagle-import:R0603")
      (libsource (lib "eagle-import") (part "rcl_334_R-EU_R0603"))
    )
    (comp (ref "R20")
      (value "100k")
      (footprint "eagle-import:R0603")
      (libsource (lib "eagle-import") (part "rcl_334_R-EU_R0603"))
    )
    (comp (ref "R21")
      (value "200")
      (footprint "eagle-import:R0603")
      (libsource (lib "eagle-import") (part "R-EU_R0603"))
    )
    (comp (ref "R23")
      (value "200")
      (footprint "eagle-import:R0603")
      (libsource (lib "eagle-import") (part "R-EU_R0603"))
    )
    (comp (ref "R24")
      (value "200")
      (footprint "eagle-import:R0603")
      (libsource (lib "eagle-import") (part "R-EU_R0603"))
    )
    (comp (ref "R25")
      (value "200")
      (footprint "eagle-import:R0603")
      (libsource (lib "eagle-import") (part "R-EU_R0603"))
    )
    (comp (ref "R26")
      (value "200")
      (footprint "eagle-import:R0603")
      (libsource (lib "eagle-import") (part "R-EU_R0603"))
    )
    (comp (ref "R27")
      (value "200")
      (footprint "eagle-import:R0603")
      (libsource (lib "eagle-import") (part "R-EU_R0603"))
    )
    (comp (ref "R28")
      (value "200")
      (footprint "eagle-import:R0603")
      (libsource (lib "eagle-import") (part "R-EU_R0603"))
    )
    (comp (ref "R29")
      (value "200")
      (footprint "eagle-import:R0603")
      (libsource (lib "eagle-import") (part "R-EU_R0603"))
    )
    (comp (ref "R30")
      (value "200")
      (footprint "eagle-import:R0603")
      (libsource (lib "eagle-import") (part "R-EU_R0603"))
    )
    (comp (ref "R32")
      (value "200")
      (footprint "eagle-import:R0603")
      (libsource (lib "eagle-import") (part "R-EU_R0603"))
    )
    (comp (ref "R33")
      (value "200")
      (footprint "eagle-import:R0603")
      (libsource (lib "eagle-import") (part "R-EU_R0603"))
    )
    (comp (ref "R34")
      (value "200")
      (footprint "eagle-import:R0603")
      (libsource (lib "eagle-import") (part "R-EU_R0603"))
    )
    (comp (ref "R35")
      (value "200")
      (footprint "eagle-import:R0603")
      (libsource (lib "eagle-import") (part "R-EU_R0603"))
    )
    (comp (ref "R36")
      (value "200")
      (footprint "eagle-import:R0603")
      (libsource (lib "eagle-import") (part "R-EU_R0603"))
    )
    (comp (ref "R37")
      (value "200")
      (footprint "eagle-import:R0603")
      (libsource (lib "eagle-import") (part "R-EU_R0603"))
    )
    (comp (ref "R38")
      (value "200")
      (footprint "eagle-import:R0603")
      (libsource (lib "eagle-import") (part "R-EU_R0603"))
    )
    (comp (ref "R39")
      (value "200")
      (footprint "eagle-import:R0603")
      (libsource (lib "eagle-import") (part "R-EU_R0603"))
    )
    (comp (ref "R40")
      (value "200")
      (footprint "eagle-import:R0603")
      (libsource (lib "eagle-import") (part "R-EU_R0603"))
    )
    (comp (ref "R41")
      (value "200")
      (footprint "eagle-import:R0603")
      (libsource (lib "eagle-import") (part "R-EU_R0603"))
    )
    (comp (ref "R42")
      (value "200")
      (footprint "eagle-import:R0603")
      (libsource (lib "eagle-import") (part "R-EU_R0603"))
    )
    (comp (ref "R43")
      (value "200")
      (footprint "eagle-import:R0603")
      (libsource (lib "eagle-import") (part "R-EU_R0603"))
    )
    (comp (ref "R44")
      (value "200")
      (footprint "eagle-import:R0603")
      (libsource (lib "eagle-import") (part "R-EU_R0603"))
    )
    (comp (ref "R45")
      (value "200")
      (footprint "eagle-import:R0603")
      (libsource (lib "eagle-import") (part "R-EU_R0603"))
    )
    (comp (ref "R46")
      (value "200")
      (footprint "eagle-import:R0603")
      (libsource (lib "eagle-import") (part "R-EU_R0603"))
    )
    (comp (ref "R47")
      (value "200")
      (footprint "eagle-import:R0603")
      (libsource (lib "eagle-import") (part "R-EU_R0603"))
    )
    (comp (ref "R48")
      (value "200")
      (footprint "eagle-import:R0603")
      (libsource (lib "eagle-import") (part "R-EU_R0603"))
    )
    (comp (ref "R49")
      (value "200")
      (footprint "eagle-import:R0603")
      (libsource (lib "eagle-import") (part "R-EU_R0603"))
    )
    (comp (ref "R50")
      (value "200")
      (footprint "eagle-import:R0603")
      (libsource (lib "eagle-import") (part "R-EU_R0603"))
    )
    (comp (ref "R51")
      (value "200")
      (footprint "eagle-import:R0603")
      (libsource (lib "eagle-import") (part "R-EU_R0603"))
    )
    (comp (ref "R52")
      (value "200")
      (footprint "eagle-import:R0603")
      (libsource (lib "eagle-import") (part "R-EU_R0603"))
    )
    (comp (ref "R53")
      (value "200")
      (footprint "eagle-import:R0603")
      (libsource (lib "eagle-import") (part "R-EU_R0603"))
    )
    (comp (ref "R54")
      (value "200")
      (footprint "eagle-import:R0603")
      (libsource (lib "eagle-import") (part "R-EU_R0603"))
    )
    (comp (ref "R55")
      (value "200")
      (footprint "eagle-import:R0603")
      (libsource (lib "eagle-import") (part "R-EU_R0603"))
    )
    (comp (ref "R57")
      (value "200")
      (footprint "eagle-import:R0603")
      (libsource (lib "eagle-import") (part "R-EU_R0603"))
    )
    (comp (ref "R58")
      (value "200")
      (footprint "eagle-import:R0603")
      (libsource (lib "eagle-import") (part "R-EU_R0603"))
    )
    (comp (ref "R59")
      (value "200")
      (footprint "eagle-import:R0603")
      (libsource (lib "eagle-import") (part "R-EU_R0603"))
    )
    (comp (ref "R60")
      (value "200")
      (footprint "eagle-import:R0603")
      (libsource (lib "eagle-import") (part "R-EU_R0603"))
    )
    (comp (ref "R61")
      (value "200")
      (footprint "eagle-import:R0603")
      (libsource (lib "eagle-import") (part "R-EU_R0603"))
    )
    (comp (ref "R62")
      (value "200")
      (footprint "eagle-import:R0603")
      (libsource (lib "eagle-import") (part "R-EU_R0603"))
    )
    (comp (ref "R63")
      (value "200")
      (footprint "eagle-import:R0603")
      (libsource (lib "eagle-import") (part "R-EU_R0603"))
    )
    (comp (ref "S5")
      (value "MOMENTARY-SWITCH-SPST-SMD-4.6X2.8MM")
      (footprint "eagle-import:TACTILE_SWITCH_SMD_4.6X2.8MM")
      (libsource (lib "eagle-import") (part "MOMENTARY-SWITCH-SPST-SMD-4.6X2.8MM"))
    )
    (comp (ref "U1")
      (value "ISP1807-LRISP1807-LR_ISP1807-LR")
      (footprint "eagle-import:ISP1807-LR")
      (fields (field (name "REF") "ISP1807-LR") (field (name "ISP_PART") "ISP1807"))
      (libsource (lib "eagle-import") (part "ISP1807-LRISP1807-LR_ISP1807-LR"))
    )
    (comp (ref "VREG")
      (value "AP2112K-3.3TRG1")
      (footprint "eagle-import:SOT95P285X140-5N")
      (fields (field (name "MF") "Diodes Inc."))
      (libsource (lib "eagle-import") (part "AP2112K-3.3TRG1"))
    )
  )
  (nets
    (net (code "1") (name "/BLED") (class "Default")
      (node (ref "LED1") (pin "A") (pinfunction "A_A") (pintype "passive"))
      (node (ref "U1") (pin "37") (pinfunction "P0.15_37") (pintype "bidirectional"))
    )
    (net (code "2") (name "/BVOLT") (class "Default")
      (node (ref "R19") (pin "2") (pinfunction "2_2") (pintype "passive"))
      (node (ref "R20") (pin "1") (pinfunction "1_1") (pintype "passive"))
      (node (ref "U1") (pin "35") (pinfunction "P0.04/AIN2_35") (pintype "bidirectional"))
    )
    (net (code "3") (name "/COL0") (class "Default")
      (node (ref "21") (pin "2") (pinfunction "2_2") (pintype "bidirectional"))
      (node (ref "31") (pin "2") (pinfunction "2_2") (pintype "bidirectional"))
      (node (ref "5") (pin "2") (pinfunction "2_2") (pintype "bidirectional"))
      (node (ref "6") (pin "2") (pinfunction "2_2") (pintype "bidirectional"))
      (node (ref "U1") (pin "6") (pinfunction "P0.26_6") (pintype "bidirectional"))
    )
    (net (code "4") (name "/COL1") (class "Default")
      (node (ref "12") (pin "2") (pinfunction "2_2") (pintype "bidirectional"))
      (node (ref "22") (pin "2") (pinfunction "2_2") (pintype "bidirectional"))
      (node (ref "32") (pin "2") (pinfunction "2_2") (pintype "bidirectional"))
      (node (ref "42") (pin "2") (pinfunction "2_2") (pintype "bidirectional"))
      (node (ref "U1") (pin "4") (pinfunction "P0.10/NFC2_4") (pintype "bidirectional"))
    )
    (net (code "5") (name "/COL2") (class "Default")
      (node (ref "13") (pin "2") (pinfunction "2_2") (pintype "bidirectional"))
      (node (ref "23") (pin "2") (pinfunction "2_2") (pintype "bidirectional"))
      (node (ref "33") (pin "2") (pinfunction "2_2") (pintype "bidirectional"))
      (node (ref "43") (pin "2") (pinfunction "2_2") (pintype "bidirectional"))
      (node (ref "U1") (pin "2") (pinfunction "P0.09/NFC1_2") (pintype "bidirectional"))
    )
    (net (code "6") (name "/COL3") (class "Default")
      (node (ref "14") (pin "2") (pinfunction "2_2") (pintype "bidirectional"))
      (node (ref "24") (pin "2") (pinfunction "2_2") (pintype "bidirectional"))
      (node (ref "34") (pin "2") (pinfunction "2_2") (pintype "bidirectional"))
      (node (ref "44") (pin "2") (pinfunction "2_2") (pintype "bidirectional"))
      (node (ref "U1") (pin "48") (pinfunction "P0.28/AIN4_48") (pintype "bidirectional"))
    )
    (net (code "7") (name "/COL4") (class "Default")
      (node (ref "15") (pin "2") (pinfunction "2_2") (pintype "bidirectional"))
      (node (ref "25") (pin "2") (pinfunction "2_2") (pintype "bidirectional"))
      (node (ref "35") (pin "2") (pinfunction "2_2") (pintype "bidirectional"))
      (node (ref "45") (pin "2") (pinfunction "2_2") (pintype "bidirectional"))
      (node (ref "U1") (pin "46") (pinfunction "P0.29/AIN5_46") (pintype "bidirectional"))
    )
    (net (code "8") (name "/COL5") (class "Default")
      (node (ref "16") (pin "2") (pinfunction "2_2") (pintype "bidirectional"))
      (node (ref "26") (pin "2") (pinfunction "2_2") (pintype "bidirectional"))
      (node (ref "36") (pin "2") (pinfunction "2_2") (pintype "bidirectional"))
      (node (ref "46") (pin "2") (pinfunction "2_2") (pintype "bidirectional"))
      (node (ref "U1") (pin "44") (pinfunction "P0.30/AIN6_44") (pintype "bidirectional"))
    )
    (net (code "9") (name "/COL6") (class "Default")
      (node (ref "17") (pin "2") (pinfunction "2_2") (pintype "bidirectional"))
      (node (ref "27") (pin "2") (pinfunction "2_2") (pintype "bidirectional"))
      (node (ref "37") (pin "2") (pinfunction "2_2") (pintype "bidirectional"))
      (node (ref "U1") (pin "42") (pinfunction "P0.31/AIN7_42") (pintype "bidirectional"))
    )
    (net (code "10") (name "/COL7") (class "Default")
      (node (ref "18") (pin "2") (pinfunction "2_2") (pintype "bidirectional"))
      (node (ref "28") (pin "2") (pinfunction "2_2") (pintype "bidirectional"))
      (node (ref "38") (pin "2") (pinfunction "2_2") (pintype "bidirectional"))
      (node (ref "47") (pin "2") (pinfunction "2_2") (pintype "bidirectional"))
      (node (ref "U1") (pin "40") (pinfunction "P0.02/AIN0_40") (pintype "bidirectional"))
    )
    (net (code "11") (name "/COL8") (class "Default")
      (node (ref "19") (pin "2") (pinfunction "2_2") (pintype "bidirectional"))
      (node (ref "29") (pin "2") (pinfunction "2_2") (pintype "bidirectional"))
      (node (ref "39") (pin "2") (pinfunction "2_2") (pintype "bidirectional"))
      (node (ref "48") (pin "2") (pinfunction "2_2") (pintype "bidirectional"))
      (node (ref "U1") (pin "38") (pinfunction "P0.03/AIN1_38") (pintype "bidirectional"))
    )
    (net (code "12") (name "/COL9") (class "Default")
      (node (ref "110") (pin "2") (pinfunction "2_2") (pintype "bidirectional"))
      (node (ref "210") (pin "2") (pinfunction "2_2") (pintype "bidirectional"))
      (node (ref "310") (pin "2") (pinfunction "2_2") (pintype "bidirectional"))
      (node (ref "49") (pin "2") (pinfunction "2_2") (pintype "bidirectional"))
      (node (ref "U1") (pin "36") (pinfunction "P0.05/AIN3_36") (pintype "bidirectional"))
    )
    (net (code "13") (name "/COL10") (class "Default")
      (node (ref "111") (pin "2") (pinfunction "2_2") (pintype "bidirectional"))
      (node (ref "211") (pin "2") (pinfunction "2_2") (pintype "bidirectional"))
      (node (ref "311") (pin "2") (pinfunction "2_2") (pintype "bidirectional"))
      (node (ref "410") (pin "2") (pinfunction "2_2") (pintype "bidirectional"))
      (node (ref "U1") (pin "34") (pinfunction "P0.06_34") (pintype "bidirectional"))
    )
    (net (code "14") (name "/COL11") (class "Default")
      (node (ref "212") (pin "2") (pinfunction "2_2") (pintype "bidirectional"))
      (node (ref "312") (pin "2") (pinfunction "2_2") (pintype "bidirectional"))
      (node (ref "7") (pin "2") (pinfunction "2_2") (pintype "bidirectional"))
      (node (ref "8") (pin "2") (pinfunction "2_2") (pintype "bidirectional"))
      (node (ref "U1") (pin "32") (pinfunction "P0.08_32") (pintype "bidirectional"))
    )
    (net (code "15") (name "/D+") (class "Default")
      (node (ref "D64") (pin "A") (pinfunction "A_A") (pintype "passive"))
      (node (ref "J3") (pin "A6") (pinfunction "D+_A6") (pintype "bidirectional"))
      (node (ref "J3") (pin "B6") (pinfunction "D+_B6") (pintype "bidirectional"))
      (node (ref "U1") (pin "8") (pinfunction "D+_8") (pintype "power_in"))
    )
    (net (code "16") (name "/D-") (class "Default")
      (node (ref "D65") (pin "A") (pinfunction "A_A") (pintype "passive"))
      (node (ref "J3") (pin "A7") (pinfunction "D-_A7") (pintype "bidirectional"))
      (node (ref "J3") (pin "B7") (pinfunction "D-_B7") (pintype "bidirectional"))
      (node (ref "U1") (pin "10") (pinfunction "D-_10") (pintype "power_in"))
    )
    (net (code "17") (name "/G_BAT") (class "Default")
      (node (ref "C5") (pin "2") (pinfunction "2_2") (pintype "passive"))
      (node (ref "IC1") (pin "3") (pinfunction "GND_3") (pintype "bidirectional"))
      (node (ref "J4") (pin "2") (pinfunction "2_2") (pintype "passive"))
    )
    (net (code "18") (name "/POWER_PIN") (class "Default")
      (node (ref "U1") (pin "29") (pinfunction "P0.13_29") (pintype "bidirectional"))
    )
    (net (code "19") (name "/PWM") (class "Default")
      (node (ref "Q7") (pin "1") (pinfunction "G_1") (pintype "passive"))
      (node (ref "R7") (pin "1") (pinfunction "1_1") (pintype "passive"))
      (node (ref "U1") (pin "55") (pinfunction "P1.08_55") (pintype "bidirectional"))
    )
    (net (code "20") (name "/RESET") (class "Default")
      (node (ref "PROG1") (pin "3") (pinfunction "3_3") (pintype "passive"))
      (node (ref "R2") (pin "2") (pinfunction "2_2") (pintype "passive"))
      (node (ref "S5") (pin "3") (pinfunction "2_3") (pintype "passive"))
      (node (ref "S5") (pin "4") (pinfunction "2_4") (pintype "passive"))
      (node (ref "U1") (pin "13") (pinfunction "P0.18/NRESET_13") (pintype "bidirectional"))
      (node (ref "U1") (pin "9") (pinfunction "P0.16_9") (pintype "bidirectional"))
    )
    (net (code "21") (name "/ROW0") (class "Default")
      (node (ref "D1") (pin "C") (pinfunction "C_C") (pintype "passive"))
      (node (ref "D10") (pin "C") (pinfunction "C_C") (pintype "passive"))
      (node (ref "D11") (pin "C") (pinfunction "C_C") (pintype "passive"))
      (node (ref "D12") (pin "C") (pinfunction "C_C") (pintype "passive"))
      (node (ref "D2") (pin "C") (pinfunction "C_C") (pintype "passive"))
      (node (ref "D3") (pin "C") (pinfunction "C_C") (pintype "passive"))
      (node (ref "D4") (pin "C") (pinfunction "C_C") (pintype "passive"))
      (node (ref "D5") (pin "C") (pinfunction "C_C") (pintype "passive"))
      (node (ref "D6") (pin "C") (pinfunction "C_C") (pintype "passive"))
      (node (ref "D7") (pin "C") (pinfunction "C_C") (pintype "passive"))
      (node (ref "D8") (pin "C") (pinfunction "C_C") (pintype "passive"))
      (node (ref "D9") (pin "C") (pinfunction "C_C") (pintype "passive"))
      (node (ref "U1") (pin "3") (pinfunction "P0.12_3") (pintype "bidirectional"))
    )
    (net (code "22") (name "/ROW1") (class "Default")
      (node (ref "D13") (pin "C") (pinfunction "C_C") (pintype "passive"))
      (node (ref "D14") (pin "C") (pinfunction "C_C") (pintype "passive"))
      (node (ref "D15") (pin "C") (pinfunction "C_C") (pintype "passive"))
      (node (ref "D16") (pin "C") (pinfunction "C_C") (pintype "passive"))
      (node (ref "D17") (pin "C") (pinfunction "C_C") (pintype "passive"))
      (node (ref "D18") (pin "C") (pinfunction "C_C") (pintype "passive"))
      (node (ref "D19") (pin "C") (pinfunction "C_C") (pintype "passive"))
      (node (ref "D20") (pin "C") (pinfunction "C_C") (pintype "passive"))
      (node (ref "D21") (pin "C") (pinfunction "C_C") (pintype "passive"))
      (node (ref "D22") (pin "C") (pinfunction "C_C") (pintype "passive"))
      (node (ref "D23") (pin "C") (pinfunction "C_C") (pintype "passive"))
      (node (ref "D24") (pin "C") (pinfunction "C_C") (pintype "passive"))
      (node (ref "U1") (pin "47") (pinfunction "P0.23_47") (pintype "bidirectional"))
    )
    (net (code "23") (name "/ROW2") (class "Default")
      (node (ref "D25") (pin "C") (pinfunction "C_C") (pintype "passive"))
      (node (ref "D26") (pin "C") (pinfunction "C_C") (pintype "passive"))
      (node (ref "D27") (pin "C") (pinfunction "C_C") (pintype "passive"))
      (node (ref "D28") (pin "C") (pinfunction "C_C") (pintype "passive"))
      (node (ref "D29") (pin "C") (pinfunction "C_C") (pintype "passive"))
      (node (ref "D30") (pin "C") (pinfunction "C_C") (pintype "passive"))
      (node (ref "D31") (pin "C") (pinfunction "C_C") (pintype "passive"))
      (node (ref "D32") (pin "C") (pinfunction "C_C") (pintype "passive"))
      (node (ref "D33") (pin "C") (pinfunction "C_C") (pintype "passive"))
      (node (ref "D34") (pin "C") (pinfunction "C_C") (pintype "passive"))
      (node (ref "D35") (pin "C") (pinfunction "C_C") (pintype "passive"))
      (node (ref "D36") (pin "C") (pinfunction "C_C") (pintype "passive"))
      (node (ref "U1") (pin "45") (pinfunction "P0.19_45") (pintype "bidirectional"))
    )
    (net (code "24") (name "/ROW3") (class "Default")
      (node (ref "D37") (pin "C") (pinfunction "C_C") (pintype "passive"))
      (node (ref "D38") (pin "C") (pinfunction "C_C") (pintype "passive"))
      (node (ref "D39") (pin "C") (pinfunction "C_C") (pintype "passive"))
      (node (ref "D40") (pin "C") (pinfunction "C_C") (pintype "passive"))
      (node (ref "D41") (pin "C") (pinfunction "C_C") (pintype "passive"))
      (node (ref "D42") (pin "C") (pinfunction "C_C") (pintype "passive"))
      (node (ref "D43") (pin "C") (pinfunction "C_C") (pintype "passive"))
      (node (ref "D44") (pin "C") (pinfunction "C_C") (pintype "passive"))
      (node (ref "D45") (pin "C") (pinfunction "C_C") (pintype "passive"))
      (node (ref "D46") (pin "C") (pinfunction "C_C") (pintype "passive"))
      (node (ref "D47") (pin "C") (pinfunction "C_C") (pintype "passive"))
      (node (ref "U1") (pin "43") (pinfunction "P0.11_43") (pintype "bidirectional"))
    )
    (net (code "25") (name "/SCK") (class "Default")
      (node (ref "PROG1") (pin "4") (pinfunction "4_4") (pintype "passive"))
      (node (ref "U1") (pin "30") (pinfunction "SWDCLK_30") (pintype "input"))
    )
    (net (code "26") (name "/SWD") (class "Default")
      (node (ref "PROG1") (pin "5") (pinfunction "5_5") (pintype "passive"))
      (node (ref "U1") (pin "28") (pinfunction "SWDIO_28") (pintype "bidirectional"))
    )
    (net (code "27") (name "/VDD_NRF") (class "Default")
      (node (ref "D66") (pin "A") (pinfunction "A_A") (pintype "passive"))
      (node (ref "PROG1") (pin "1") (pinfunction "1_1") (pintype "passive"))
      (node (ref "R2") (pin "1") (pinfunction "1_1") (pintype "passive"))
      (node (ref "U1") (pin "26") (pinfunction "VCC_NRF_26") (pintype "power_in"))
      (node (ref "VREG") (pin "5") (pinfunction "VOUT_5") (pintype "power_in"))
    )
    (net (code "28") (name "/V_LED") (class "Default")
      (node (ref "Q1") (pin "3") (pinfunction "D_3") (pintype "passive"))
      (node (ref "R10") (pin "2") (pinfunction "2_2") (pintype "passive"))
      (node (ref "R16") (pin "2") (pinfunction "2_2") (pintype "passive"))
      (node (ref "R18") (pin "2") (pinfunction "2_2") (pintype "passive"))
      (node (ref "R21") (pin "2") (pinfunction "2_2") (pintype "passive"))
      (node (ref "R23") (pin "2") (pinfunction "2_2") (pintype "passive"))
      (node (ref "R24") (pin "2") (pinfunction "2_2") (pintype "passive"))
      (node (ref "R25") (pin "2") (pinfunction "2_2") (pintype "passive"))
      (node (ref "R26") (pin "2") (pinfunction "2_2") (pintype "passive"))
      (node (ref "R27") (pin "2") (pinfunction "2_2") (pintype "passive"))
      (node (ref "R28") (pin "2") (pinfunction "2_2") (pintype "passive"))
      (node (ref "R29") (pin "2") (pinfunction "2_2") (pintype "passive"))
      (node (ref "R30") (pin "2") (pinfunction "2_2") (pintype "passive"))
      (node (ref "R32") (pin "2") (pinfunction "2_2") (pintype "passive"))
      (node (ref "R33") (pin "2") (pinfunction "2_2") (pintype "passive"))
      (node (ref "R34") (pin "2") (pinfunction "2_2") (pintype "passive"))
      (node (ref "R35") (pin "2") (pinfunction "2_2") (pintype "passive"))
      (node (ref "R36") (pin "2") (pinfunction "2_2") (pintype "passive"))
      (node (ref "R37") (pin "2") (pinfunction "2_2") (pintype "passive"))
      (node (ref "R38") (pin "2") (pinfunction "2_2") (pintype "passive"))
      (node (ref "R39") (pin "2") (pinfunction "2_2") (pintype "passive"))
      (node (ref "R40") (pin "2") (pinfunction "2_2") (pintype "passive"))
      (node (ref "R41") (pin "2") (pinfunction "2_2") (pintype "passive"))
      (node (ref "R42") (pin "2") (pinfunction "2_2") (pintype "passive"))
      (node (ref "R43") (pin "2") (pinfunction "2_2") (pintype "passive"))
      (node (ref "R44") (pin "2") (pinfunction "2_2") (pintype "passive"))
      (node (ref "R45") (pin "2") (pinfunction "2_2") (pintype "passive"))
      (node (ref "R46") (pin "2") (pinfunction "2_2") (pintype "passive"))
      (node (ref "R47") (pin "2") (pinfunction "2_2") (pintype "passive"))
      (node (ref "R48") (pin "2") (pinfunction "2_2") (pintype "passive"))
      (node (ref "R49") (pin "2") (pinfunction "2_2") (pintype "passive"))
      (node (ref "R5") (pin "2") (pinfunction "2_2") (pintype "passive"))
      (node (ref "R50") (pin "2") (pinfunction "2_2") (pintype "passive"))
      (node (ref "R51") (pin "2") (pinfunction "2_2") (pintype "passive"))
      (node (ref "R52") (pin "2") (pinfunction "2_2") (pintype "passive"))
      (node (ref "R53") (pin "2") (pinfunction "2_2") (pintype "passive"))
      (node (ref "R54") (pin "2") (pinfunction "2_2") (pintype "passive"))
      (node (ref "R55") (pin "2") (pinfunction "2_2") (pintype "passive"))
      (node (ref "R57") (pin "2") (pinfunction "2_2") (pintype "passive"))
      (node (ref "R58") (pin "2") (pinfunction "2_2") (pintype "passive"))
      (node (ref "R59") (pin "2") (pinfunction "2_2") (pintype "passive"))
      (node (ref "R6") (pin "2") (pinfunction "2_2") (pintype "passive"))
      (node (ref "R60") (pin "2") (pinfunction "2_2") (pintype "passive"))
      (node (ref "R61") (pin "2") (pinfunction "2_2") (pintype "passive"))
      (node (ref "R62") (pin "2") (pinfunction "2_2") (pintype "passive"))
      (node (ref "R63") (pin "2") (pinfunction "2_2") (pintype "passive"))
      (node (ref "R8") (pin "2") (pinfunction "2_2") (pintype "passive"))
      (node (ref "R9") (pin "2") (pinfunction "2_2") (pintype "passive"))
    )
    (net (code "29") (name "/V_RAW") (class "Default")
      (node (ref "C6") (pin "1") (pinfunction "1_1") (pintype "passive"))
      (node (ref "D63") (pin "1") (pinfunction "K_1") (pintype "bidirectional"))
      (node (ref "Q1") (pin "2") (pinfunction "S_2") (pintype "passive"))
      (node (ref "Q5") (pin "2") (pinfunction "S_2") (pintype "passive"))
      (node (ref "R3") (pin "1") (pinfunction "1_1") (pintype "passive"))
      (node (ref "VREG") (pin "1") (pinfunction "VIN_1") (pintype "power_in"))
      (node (ref "VREG") (pin "3") (pinfunction "EN_3") (pintype "input"))
    )
    (net (code "30") (name "GND") (class "Default")
      (node (ref "C4") (pin "2") (pinfunction "2_2") (pintype "passive"))
      (node (ref "C6") (pin "2") (pinfunction "2_2") (pintype "passive"))
      (node (ref "D64") (pin "C") (pinfunction "C_C") (pintype "passive"))
      (node (ref "D65") (pin "C") (pinfunction "C_C") (pintype "passive"))
      (node (ref "D66") (pin "C") (pinfunction "C_C") (pintype "passive"))
      (node (ref "D67") (pin "C") (pinfunction "C_C") (pintype "passive"))
      (node (ref "IC1") (pin "1") (pinfunction "VM_1") (pintype "bidirectional"))
      (node (ref "IC2") (pin "2") (pinfunction "GND_2") (pintype "bidirectional"))
      (node (ref "J1") (pin "MP1") (pinfunction "MP1_MP1") (pintype "bidirectional"))
      (node (ref "J1") (pin "MP2") (pinfunction "MP2_MP2") (pintype "bidirectional"))
      (node (ref "J1") (pin "MP3") (pinfunction "MP3_MP3") (pintype "bidirectional"))
      (node (ref "J1") (pin "MP4") (pinfunction "MP4_MP4") (pintype "bidirectional"))
      (node (ref "J3") (pin "GND") (pinfunction "GND_GND") (pintype "bidirectional"))
      (node (ref "J3") (pin "GND2") (pinfunction "GND_GND2") (pintype "bidirectional"))
      (node (ref "J3") (pin "SHLD1") (pinfunction "SHLD_SHLD1") (pintype "bidirectional"))
      (node (ref "J3") (pin "SHLD2") (pinfunction "SHLD_SHLD2") (pintype "bidirectional"))
      (node (ref "J3") (pin "SHLD3") (pinfunction "SHLD_SHLD3") (pintype "bidirectional"))
      (node (ref "J3") (pin "SHLD4") (pinfunction "SHLD_SHLD4") (pintype "bidirectional"))
      (node (ref "J3") (pin "SHLD5") (pinfunction "SHLD_SHLD5") (pintype "bidirectional"))
      (node (ref "J3") (pin "SHLD6") (pinfunction "SHLD_SHLD6") (pintype "bidirectional"))
      (node (ref "J3") (pin "SHLD7") (pinfunction "SHLD_SHLD7") (pintype "bidirectional"))
      (node (ref "J3") (pin "SHLD8") (pinfunction "SHLD_SHLD8") (pintype "bidirectional"))
      (node (ref "LED10") (pin "2") (pinfunction "C_2") (pintype "passive"))
      (node (ref "LED12") (pin "2") (pinfunction "C_2") (pintype "passive"))
      (node (ref "LED13") (pin "2") (pinfunction "C_2") (pintype "passive"))
      (node (ref "LED14") (pin "2") (pinfunction "C_2") (pintype "passive"))
      (node (ref "LED15") (pin "2") (pinfunction "C_2") (pintype "passive"))
      (node (ref "LED16") (pin "2") (pinfunction "C_2") (pintype "passive"))
      (node (ref "LED17") (pin "2") (pinfunction "C_2") (pintype "passive"))
      (node (ref "LED18") (pin "2") (pinfunction "C_2") (pintype "passive"))
      (node (ref "LED19") (pin "2") (pinfunction "C_2") (pintype "passive"))
      (node (ref "LED21") (pin "2") (pinfunction "C_2") (pintype "passive"))
      (node (ref "LED22") (pin "2") (pinfunction "C_2") (pintype "passive"))
      (node (ref "LED23") (pin "2") (pinfunction "C_2") (pintype "passive"))
      (node (ref "LED24") (pin "2") (pinfunction "C_2") (pintype "passive"))
      (node (ref "LED25") (pin "2") (pinfunction "C_2") (pintype "passive"))
      (node (ref "LED26") (pin "2") (pinfunction "C_2") (pintype "passive"))
      (node (ref "LED27") (pin "2") (pinfunction "C_2") (pintype "passive"))
      (node (ref "LED28") (pin "2") (pinfunction "C_2") (pintype "passive"))
      (node (ref "LED29") (pin "2") (pinfunction "C_2") (pintype "passive"))
      (node (ref "LED3") (pin "2") (pinfunction "C_2") (pintype "passive"))
      (node (ref "LED30") (pin "2") (pinfunction "C_2") (pintype "passive"))
      (node (ref "LED31") (pin "2") (pinfunction "C_2") (pintype "passive"))
      (node (ref "LED32") (pin "2") (pinfunction "C_2") (pintype "passive"))
      (node (ref "LED33") (pin "2") (pinfunction "C_2") (pintype "passive"))
      (node (ref "LED34") (pin "2") (pinfunction "C_2") (pintype "passive"))
      (node (ref "LED35") (pin "2") (pinfunction "C_2") (pintype "passive"))
      (node (ref "LED36") (pin "2") (pinfunction "C_2") (pintype "passive"))
      (node (ref "LED37") (pin "2") (pinfunction "C_2") (pintype "passive"))
      (node (ref "LED38") (pin "2") (pinfunction "C_2") (pintype "passive"))
      (node (ref "LED39") (pin "2") (pinfunction "C_2") (pintype "passive"))
      (node (ref "LED4") (pin "2") (pinfunction "C_2") (pintype "passive"))
      (node (ref "LED40") (pin "2") (pinfunction "C_2") (pintype "passive"))
      (node (ref "LED41") (pin "2") (pinfunction "C_2") (pintype "passive"))
      (node (ref "LED42") (pin "2") (pinfunction "C_2") (pintype "passive"))
      (node (ref "LED43") (pin "2") (pinfunction "C_2") (pintype "passive"))
      (node (ref "LED44") (pin "2") (pinfunction "C_2") (pintype "passive"))
      (node (ref "LED46") (pin "2") (pinfunction "C_2") (pintype "passive"))
      (node (ref "LED47") (pin "2") (pinfunction "C_2") (pintype "passive"))
      (node (ref "LED48") (pin "2") (pinfunction "C_2") (pintype "passive"))
      (node (ref "LED49") (pin "2") (pinfunction "C_2") (pintype "passive"))
      (node (ref "LED5") (pin "2") (pinfunction "C_2") (pintype "passive"))
      (node (ref "LED50") (pin "2") (pinfunction "C_2") (pintype "passive"))
      (node (ref "LED51") (pin "2") (pinfunction "C_2") (pintype "passive"))
      (node (ref "LED52") (pin "2") (pinfunction "C_2") (pintype "passive"))
      (node (ref "LED6") (pin "2") (pinfunction "C_2") (pintype "passive"))
      (node (ref "LED7") (pin "2") (pinfunction "C_2") (pintype "passive"))
      (node (ref "LED8") (pin "2") (pinfunction "C_2") (pintype "passive"))
      (node (ref "LED9") (pin "2") (pinfunction "C_2") (pintype "passive"))
      (node (ref "PROG1") (pin "2") (pinfunction "2_2") (pintype "passive"))
      (node (ref "Q7") (pin "2") (pinfunction "S_2") (pintype "passive"))
      (node (ref "R1") (pin "1") (pinfunction "1_1") (pintype "passive"))
      (node (ref "R11") (pin "1") (pinfunction "1_1") (pintype "passive"))
      (node (ref "R12") (pin "1") (pinfunction "1_1") (pintype "passive"))
      (node (ref "R13") (pin "1") (pinfunction "1_1") (pintype "passive"))
      (node (ref "R17") (pin "1") (pinfunction "1_1") (pintype "passive"))
      (node (ref "R20") (pin "2") (pinfunction "2_2") (pintype "passive"))
      (node (ref "R4") (pin "1") (pinfunction "1_1") (pintype "passive"))
      (node (ref "R7") (pin "2") (pinfunction "2_2") (pintype "passive"))
      (node (ref "S5") (pin "1") (pinfunction "1_1") (pintype "passive"))
      (node (ref "S5") (pin "2") (pinfunction "1_2") (pintype "passive"))
      (node (ref "U1") (pin "1") (pinfunction "VSS_1") (pintype "power_in"))
      (node (ref "U1") (pin "14") (pinfunction "VSS_14") (pintype "power_in"))
      (node (ref "U1") (pin "16") (pinfunction "VSS_16") (pintype "power_in"))
      (node (ref "U1") (pin "18") (pinfunction "VSS_18") (pintype "power_in"))
      (node (ref "U1") (pin "19") (pinfunction "P0.24_19") (pintype "bidirectional"))
      (node (ref "U1") (pin "21") (pinfunction "VSS_21") (pintype "power_in"))
      (node (ref "U1") (pin "23") (pinfunction "VSS_23") (pintype "power_in"))
      (node (ref "U1") (pin "24") (pinfunction "VSS_24") (pintype "power_in"))
      (node (ref "U1") (pin "25") (pinfunction "VSS_25") (pintype "power_in"))
      (node (ref "U1") (pin "31") (pinfunction "VSS_31") (pintype "power_in"))
      (node (ref "U1") (pin "7") (pinfunction "VSS_7") (pintype "power_in"))
      (node (ref "VREG") (pin "2") (pinfunction "GND_2") (pintype "power_in"))
    )
    (net (code "31") (name "Net-(5-Pad1)") (class "Default")
      (node (ref "5") (pin "1") (pinfunction "1_1") (pintype "bidirectional"))
      (node (ref "D1") (pin "A") (pinfunction "A_A") (pintype "passive"))
    )
    (net (code "32") (name "Net-(6-Pad1)") (class "Default")
      (node (ref "6") (pin "1") (pinfunction "1_1") (pintype "bidirectional"))
      (node (ref "D37") (pin "A") (pinfunction "A_A") (pintype "passive"))
    )
    (net (code "33") (name "Net-(7-Pad1)") (class "Default")
      (node (ref "7") (pin "1") (pinfunction "1_1") (pintype "bidirectional"))
      (node (ref "D47") (pin "A") (pinfunction "A_A") (pintype "passive"))
    )
    (net (code "34") (name "Net-(8-Pad1)") (class "Default")
      (node (ref "8") (pin "1") (pinfunction "1_1") (pintype "bidirectional"))
      (node (ref "D12") (pin "A") (pinfunction "A_A") (pintype "passive"))
    )
    (net (code "35") (name "Net-(12-Pad1)") (class "Default")
      (node (ref "12") (pin "1") (pinfunction "1_1") (pintype "bidirectional"))
      (node (ref "D2") (pin "A") (pinfunction "A_A") (pintype "passive"))
    )
    (net (code "36") (name "Net-(13-Pad1)") (class "Default")
      (node (ref "13") (pin "1") (pinfunction "1_1") (pintype "bidirectional"))
      (node (ref "D3") (pin "A") (pinfunction "A_A") (pintype "passive"))
    )
    (net (code "37") (name "Net-(14-Pad1)") (class "Default")
      (node (ref "14") (pin "1") (pinfunction "1_1") (pintype "bidirectional"))
      (node (ref "D4") (pin "A") (pinfunction "A_A") (pintype "passive"))
    )
    (net (code "38") (name "Net-(15-Pad1)") (class "Default")
      (node (ref "15") (pin "1") (pinfunction "1_1") (pintype "bidirectional"))
      (node (ref "D5") (pin "A") (pinfunction "A_A") (pintype "passive"))
    )
    (net (code "39") (name "Net-(16-Pad1)") (class "Default")
      (node (ref "16") (pin "1") (pinfunction "1_1") (pintype "bidirectional"))
      (node (ref "D6") (pin "A") (pinfunction "A_A") (pintype "passive"))
    )
    (net (code "40") (name "Net-(17-Pad1)") (class "Default")
      (node (ref "17") (pin "1") (pinfunction "1_1") (pintype "bidirectional"))
      (node (ref "D7") (pin "A") (pinfunction "A_A") (pintype "passive"))
    )
    (net (code "41") (name "Net-(18-Pad1)") (class "Default")
      (node (ref "18") (pin "1") (pinfunction "1_1") (pintype "bidirectional"))
      (node (ref "D8") (pin "A") (pinfunction "A_A") (pintype "passive"))
    )
    (net (code "42") (name "Net-(19-Pad1)") (class "Default")
      (node (ref "19") (pin "1") (pinfunction "1_1") (pintype "bidirectional"))
      (node (ref "D9") (pin "A") (pinfunction "A_A") (pintype "passive"))
    )
    (net (code "43") (name "Net-(21-Pad1)") (class "Default")
      (node (ref "21") (pin "1") (pinfunction "1_1") (pintype "bidirectional"))
      (node (ref "D13") (pin "A") (pinfunction "A_A") (pintype "passive"))
    )
    (net (code "44") (name "Net-(22-Pad1)") (class "Default")
      (node (ref "22") (pin "1") (pinfunction "1_1") (pintype "bidirectional"))
      (node (ref "D14") (pin "A") (pinfunction "A_A") (pintype "passive"))
    )
    (net (code "45") (name "Net-(23-Pad1)") (class "Default")
      (node (ref "23") (pin "1") (pinfunction "1_1") (pintype "bidirectional"))
      (node (ref "D15") (pin "A") (pinfunction "A_A") (pintype "passive"))
    )
    (net (code "46") (name "Net-(24-Pad1)") (class "Default")
      (node (ref "24") (pin "1") (pinfunction "1_1") (pintype "bidirectional"))
      (node (ref "D16") (pin "A") (pinfunction "A_A") (pintype "passive"))
    )
    (net (code "47") (name "Net-(25-Pad1)") (class "Default")
      (node (ref "25") (pin "1") (pinfunction "1_1") (pintype "bidirectional"))
      (node (ref "D17") (pin "A") (pinfunction "A_A") (pintype "passive"))
    )
    (net (code "48") (name "Net-(26-Pad1)") (class "Default")
      (node (ref "26") (pin "1") (pinfunction "1_1") (pintype "bidirectional"))
      (node (ref "D18") (pin "A") (pinfunction "A_A") (pintype "passive"))
    )
    (net (code "49") (name "Net-(27-Pad1)") (class "Default")
      (node (ref "27") (pin "1") (pinfunction "1_1") (pintype "bidirectional"))
      (node (ref "D19") (pin "A") (pinfunction "A_A") (pintype "passive"))
    )
    (net (code "50") (name "Net-(28-Pad1)") (class "Default")
      (node (ref "28") (pin "1") (pinfunction "1_1") (pintype "bidirectional"))
      (node (ref "D20") (pin "A") (pinfunction "A_A") (pintype "passive"))
    )
    (net (code "51") (name "Net-(29-Pad1)") (class "Default")
      (node (ref "29") (pin "1") (pinfunction "1_1") (pintype "bidirectional"))
      (node (ref "D21") (pin "A") (pinfunction "A_A") (pintype "passive"))
    )
    (net (code "52") (name "Net-(31-Pad1)") (class "Default")
      (node (ref "31") (pin "1") (pinfunction "1_1") (pintype "bidirectional"))
      (node (ref "D25") (pin "A") (pinfunction "A_A") (pintype "passive"))
    )
    (net (code "53") (name "Net-(32-Pad1)") (class "Default")
      (node (ref "32") (pin "1") (pinfunction "1_1") (pintype "bidirectional"))
      (node (ref "D26") (pin "A") (pinfunction "A_A") (pintype "passive"))
    )
    (net (code "54") (name "Net-(33-Pad1)") (class "Default")
      (node (ref "33") (pin "1") (pinfunction "1_1") (pintype "bidirectional"))
      (node (ref "D27") (pin "A") (pinfunction "A_A") (pintype "passive"))
    )
    (net (code "55") (name "Net-(34-Pad1)") (class "Default")
      (node (ref "34") (pin "1") (pinfunction "1_1") (pintype "bidirectional"))
      (node (ref "D28") (pin "A") (pinfunction "A_A") (pintype "passive"))
    )
    (net (code "56") (name "Net-(35-Pad1)") (class "Default")
      (node (ref "35") (pin "1") (pinfunction "1_1") (pintype "bidirectional"))
      (node (ref "D29") (pin "A") (pinfunction "A_A") (pintype "passive"))
    )
    (net (code "57") (name "Net-(36-Pad1)") (class "Default")
      (node (ref "36") (pin "1") (pinfunction "1_1") (pintype "bidirectional"))
      (node (ref "D30") (pin "A") (pinfunction "A_A") (pintype "passive"))
    )
    (net (code "58") (name "Net-(37-Pad1)") (class "Default")
      (node (ref "37") (pin "1") (pinfunction "1_1") (pintype "bidirectional"))
      (node (ref "D31") (pin "A") (pinfunction "A_A") (pintype "passive"))
    )
    (net (code "59") (name "Net-(38-Pad1)") (class "Default")
      (node (ref "38") (pin "1") (pinfunction "1_1") (pintype "bidirectional"))
      (node (ref "D32") (pin "A") (pinfunction "A_A") (pintype "passive"))
    )
    (net (code "60") (name "Net-(39-Pad1)") (class "Default")
      (node (ref "39") (pin "1") (pinfunction "1_1") (pintype "bidirectional"))
      (node (ref "D33") (pin "A") (pinfunction "A_A") (pintype "passive"))
    )
    (net (code "61") (name "Net-(42-Pad1)") (class "Default")
      (node (ref "42") (pin "1") (pinfunction "1_1") (pintype "bidirectional"))
      (node (ref "D38") (pin "A") (pinfunction "A_A") (pintype "passive"))
    )
    (net (code "62") (name "Net-(43-Pad1)") (class "Default")
      (node (ref "43") (pin "1") (pinfunction "1_1") (pintype "bidirectional"))
      (node (ref "D39") (pin "A") (pinfunction "A_A") (pintype "passive"))
    )
    (net (code "63") (name "Net-(44-Pad1)") (class "Default")
      (node (ref "44") (pin "1") (pinfunction "1_1") (pintype "bidirectional"))
      (node (ref "D40") (pin "A") (pinfunction "A_A") (pintype "passive"))
    )
    (net (code "64") (name "Net-(45-Pad1)") (class "Default")
      (node (ref "45") (pin "1") (pinfunction "1_1") (pintype "bidirectional"))
      (node (ref "D41") (pin "A") (pinfunction "A_A") (pintype "passive"))
    )
    (net (code "65") (name "Net-(46-Pad1)") (class "Default")
      (node (ref "46") (pin "1") (pinfunction "1_1") (pintype "bidirectional"))
      (node (ref "D42") (pin "A") (pinfunction "A_A") (pintype "passive"))
    )
    (net (code "66") (name "Net-(47-Pad1)") (class "Default")
      (node (ref "47") (pin "1") (pinfunction "1_1") (pintype "bidirectional"))
      (node (ref "D43") (pin "A") (pinfunction "A_A") (pintype "passive"))
    )
    (net (code "67") (name "Net-(48-Pad1)") (class "Default")
      (node (ref "48") (pin "1") (pinfunction "1_1") (pintype "bidirectional"))
      (node (ref "D44") (pin "A") (pinfunction "A_A") (pintype "passive"))
    )
    (net (code "68") (name "Net-(49-Pad1)") (class "Default")
      (node (ref "49") (pin "1") (pinfunction "1_1") (pintype "bidirectional"))
      (node (ref "D45") (pin "A") (pinfunction "A_A") (pintype "passive"))
    )
    (net (code "69") (name "Net-(110-Pad1)") (class "Default")
      (node (ref "110") (pin "1") (pinfunction "1_1") (pintype "bidirectional"))
      (node (ref "D10") (pin "A") (pinfunction "A_A") (pintype "passive"))
    )
    (net (code "70") (name "Net-(111-Pad1)") (class "Default")
      (node (ref "111") (pin "1") (pinfunction "1_1") (pintype "bidirectional"))
      (node (ref "D11") (pin "A") (pinfunction "A_A") (pintype "passive"))
    )
    (net (code "71") (name "Net-(210-Pad1)") (class "Default")
      (node (ref "210") (pin "1") (pinfunction "1_1") (pintype "bidirectional"))
      (node (ref "D22") (pin "A") (pinfunction "A_A") (pintype "passive"))
    )
    (net (code "72") (name "Net-(211-Pad1)") (class "Default")
      (node (ref "211") (pin "1") (pinfunction "1_1") (pintype "bidirectional"))
      (node (ref "D23") (pin "A") (pinfunction "A_A") (pintype "passive"))
    )
    (net (code "73") (name "Net-(212-Pad1)") (class "Default")
      (node (ref "212") (pin "1") (pinfunction "1_1") (pintype "bidirectional"))
      (node (ref "D24") (pin "A") (pinfunction "A_A") (pintype "passive"))
    )
    (net (code "74") (name "Net-(310-Pad1)") (class "Default")
      (node (ref "310") (pin "1") (pinfunction "1_1") (pintype "bidirectional"))
      (node (ref "D34") (pin "A") (pinfunction "A_A") (pintype "passive"))
    )
    (net (code "75") (name "Net-(311-Pad1)") (class "Default")
      (node (ref "311") (pin "1") (pinfunction "1_1") (pintype "bidirectional"))
      (node (ref "D35") (pin "A") (pinfunction "A_A") (pintype "passive"))
    )
    (net (code "76") (name "Net-(312-Pad1)") (class "Default")
      (node (ref "312") (pin "1") (pinfunction "1_1") (pintype "bidirectional"))
      (node (ref "D36") (pin "A") (pinfunction "A_A") (pintype "passive"))
    )
    (net (code "77") (name "Net-(410-Pad1)") (class "Default")
      (node (ref "410") (pin "1") (pinfunction "1_1") (pintype "bidirectional"))
      (node (ref "D46") (pin "A") (pinfunction "A_A") (pintype "passive"))
    )
    (net (code "78") (name "Net-(FUSE-Pad2)") (class "Default")
      (node (ref "FUSE") (pin "2") (pinfunction "2_2") (pintype "passive"))
      (node (ref "J3") (pin "VBUS1") (pinfunction "VBUS_VBUS1") (pintype "bidirectional"))
      (node (ref "J3") (pin "VBUS2") (pinfunction "VBUS_VBUS2") (pintype "bidirectional"))
    )
    (net (code "79") (name "Net-(IC1-VDD)") (class "Default")
      (node (ref "C5") (pin "1") (pinfunction "1_1") (pintype "passive"))
      (node (ref "IC1") (pin "2") (pinfunction "VDD_2") (pintype "bidirectional"))
      (node (ref "R15") (pin "1") (pinfunction "1_1") (pintype "passive"))
    )
    (net (code "80") (name "Net-(IC2-PROG)") (class "Default")
      (node (ref "IC2") (pin "5") (pinfunction "PROG_5") (pintype "bidirectional"))
      (node (ref "R13") (pin "2") (pinfunction "2_2") (pintype "passive"))
    )
    (net (code "81") (name "Net-(IC2-~{CHRG})") (class "Default")
      (node (ref "IC2") (pin "1") (pinfunction "~{CHRG}_1") (pintype "bidirectional"))
      (node (ref "R14") (pin "2") (pinfunction "2_2") (pintype "passive"))
    )
    (net (code "82") (name "Net-(J1-COM)") (class "Default")
      (node (ref "J1") (pin "2") (pinfunction "COM_2") (pintype "bidirectional"))
      (node (ref "Q2") (pin "1") (pinfunction "G_1") (pintype "passive"))
      (node (ref "R4") (pin "2") (pinfunction "2_2") (pintype "passive"))
    )
    (net (code "83") (name "Net-(J3-CC1)") (class "Default")
      (node (ref "J3") (pin "A5") (pinfunction "CC1_A5") (pintype "bidirectional"))
      (node (ref "R12") (pin "2") (pinfunction "2_2") (pintype "passive"))
    )
    (net (code "84") (name "Net-(J3-CC2)") (class "Default")
      (node (ref "J3") (pin "B5") (pinfunction "CC2_B5") (pintype "bidirectional"))
      (node (ref "R11") (pin "2") (pinfunction "2_2") (pintype "passive"))
    )
    (net (code "85") (name "Net-(LED1-PadC)") (class "Default")
      (node (ref "LED1") (pin "C") (pinfunction "C_C") (pintype "passive"))
      (node (ref "R1") (pin "2") (pinfunction "2_2") (pintype "passive"))
    )
    (net (code "86") (name "Net-(LED2-PadC)") (class "Default")
      (node (ref "LED2") (pin "C") (pinfunction "C_C") (pintype "passive"))
      (node (ref "R14") (pin "1") (pinfunction "1_1") (pintype "passive"))
    )
    (net (code "87") (name "Net-(LED3-A)") (class "Default")
      (node (ref "LED3") (pin "1") (pinfunction "A_1") (pintype "passive"))
      (node (ref "R5") (pin "1") (pinfunction "1_1") (pintype "passive"))
    )
    (net (code "88") (name "Net-(LED4-A)") (class "Default")
      (node (ref "LED4") (pin "1") (pinfunction "A_1") (pintype "passive"))
      (node (ref "R6") (pin "1") (pinfunction "1_1") (pintype "passive"))
    )
    (net (code "89") (name "Net-(LED5-A)") (class "Default")
      (node (ref "LED5") (pin "1") (pinfunction "A_1") (pintype "passive"))
      (node (ref "R8") (pin "1") (pinfunction "1_1") (pintype "passive"))
    )
    (net (code "90") (name "Net-(LED6-A)") (class "Default")
      (node (ref "LED6") (pin "1") (pinfunction "A_1") (pintype "passive"))
      (node (ref "R9") (pin "1") (pinfunction "1_1") (pintype "passive"))
    )
    (net (code "91") (name "Net-(LED7-A)") (class "Default")
      (node (ref "LED7") (pin "1") (pinfunction "A_1") (pintype "passive"))
      (node (ref "R10") (pin "1") (pinfunction "1_1") (pintype "passive"))
    )
    (net (code "92") (name "Net-(LED8-A)") (class "Default")
      (node (ref "LED8") (pin "1") (pinfunction "A_1") (pintype "passive"))
      (node (ref "R16") (pin "1") (pinfunction "1_1") (pintype "passive"))
    )
    (net (code "93") (name "Net-(LED9-A)") (class "Default")
      (node (ref "LED9") (pin "1") (pinfunction "A_1") (pintype "passive"))
      (node (ref "R18") (pin "1") (pinfunction "1_1") (pintype "passive"))
    )
    (net (code "94") (name "Net-(LED10-A)") (class "Default")
      (node (ref "LED10") (pin "1") (pinfunction "A_1") (pintype "passive"))
      (node (ref "R21") (pin "1") (pinfunction "1_1") (pintype "passive"))
    )
    (net (code "95") (name "Net-(LED12-A)") (class "Default")
      (node (ref "LED12") (pin "1") (pinfunction "A_1") (pintype "passive"))
      (node (ref "R23") (pin "1") (pinfunction "1_1") (pintype "passive"))
    )
    (net (code "96") (name "Net-(LED13-A)") (class "Default")
      (node (ref "LED13") (pin "1") (pinfunction "A_1") (pintype "passive"))
      (node (ref "R24") (pin "1") (pinfunction "1_1") (pintype "passive"))
    )
    (net (code "97") (name "Net-(LED14-A)") (class "Default")
      (node (ref "LED14") (pin "1") (pinfunction "A_1") (pintype "passive"))
      (node (ref "R25") (pin "1") (pinfunction "1_1") (pintype "passive"))
    )
    (net (code "98") (name "Net-(LED15-A)") (class "Default")
      (node (ref "LED15") (pin "1") (pinfunction "A_1") (pintype "passive"))
      (node (ref "R26") (pin "1") (pinfunction "1_1") (pintype "passive"))
    )
    (net (code "99") (name "Net-(LED16-A)") (class "Default")
      (node (ref "LED16") (pin "1") (pinfunction "A_1") (pintype "passive"))
      (node (ref "R27") (pin "1") (pinfunction "1_1") (pintype "passive"))
    )
    (net (code "100") (name "Net-(LED17-A)") (class "Default")
      (node (ref "LED17") (pin "1") (pinfunction "A_1") (pintype "passive"))
      (node (ref "R28") (pin "1") (pinfunction "1_1") (pintype "passive"))
    )
    (net (code "101") (name "Net-(LED18-A)") (class "Default")
      (node (ref "LED18") (pin "1") (pinfunction "A_1") (pintype "passive"))
      (node (ref "R29") (pin "1") (pinfunction "1_1") (pintype "passive"))
    )
    (net (code "102") (name "Net-(LED19-A)") (class "Default")
      (node (ref "LED19") (pin "1") (pinfunction "A_1") (pintype "passive"))
      (node (ref "R30") (pin "1") (pinfunction "1_1") (pintype "passive"))
    )
    (net (code "103") (name "Net-(LED21-A)") (class "Default")
      (node (ref "LED21") (pin "1") (pinfunction "A_1") (pintype "passive"))
      (node (ref "R32") (pin "1") (pinfunction "1_1") (pintype "passive"))
    )
    (net (code "104") (name "Net-(LED22-A)") (class "Default")
      (node (ref "LED22") (pin "1") (pinfunction "A_1") (pintype "passive"))
      (node (ref "R33") (pin "1") (pinfunction "1_1") (pintype "passive"))
    )
    (net (code "105") (name "Net-(LED23-A)") (class "Default")
      (node (ref "LED23") (pin "1") (pinfunction "A_1") (pintype "passive"))
      (node (ref "R34") (pin "1") (pinfunction "1_1") (pintype "passive"))
    )
    (net (code "106") (name "Net-(LED24-A)") (class "Default")
      (node (ref "LED24") (pin "1") (pinfunction "A_1") (pintype "passive"))
      (node (ref "R35") (pin "1") (pinfunction "1_1") (pintype "passive"))
    )
    (net (code "107") (name "Net-(LED25-A)") (class "Default")
      (node (ref "LED25") (pin "1") (pinfunction "A_1") (pintype "passive"))
      (node (ref "R36") (pin "1") (pinfunction "1_1") (pintype "passive"))
    )
    (net (code "108") (name "Net-(LED26-A)") (class "Default")
      (node (ref "LED26") (pin "1") (pinfunction "A_1") (pintype "passive"))
      (node (ref "R37") (pin "1") (pinfunction "1_1") (pintype "passive"))
    )
    (net (code "109") (name "Net-(LED27-A)") (class "Default")
      (node (ref "LED27") (pin "1") (pinfunction "A_1") (pintype "passive"))
      (node (ref "R38") (pin "1") (pinfunction "1_1") (pintype "passive"))
    )
    (net (code "110") (name "Net-(LED28-A)") (class "Default")
      (node (ref "LED28") (pin "1") (pinfunction "A_1") (pintype "passive"))
      (node (ref "R39") (pin "1") (pinfunction "1_1") (pintype "passive"))
    )
    (net (code "111") (name "Net-(LED29-A)") (class "Default")
      (node (ref "LED29") (pin "1") (pinfunction "A_1") (pintype "passive"))
      (node (ref "R40") (pin "1") (pinfunction "1_1") (pintype "passive"))
    )
    (net (code "112") (name "Net-(LED30-A)") (class "Default")
      (node (ref "LED30") (pin "1") (pinfunction "A_1") (pintype "passive"))
      (node (ref "R41") (pin "1") (pinfunction "1_1") (pintype "passive"))
    )
    (net (code "113") (name "Net-(LED31-A)") (class "Default")
      (node (ref "LED31") (pin "1") (pinfunction "A_1") (pintype "passive"))
      (node (ref "R42") (pin "1") (pinfunction "1_1") (pintype "passive"))
    )
    (net (code "114") (name "Net-(LED32-A)") (class "Default")
      (node (ref "LED32") (pin "1") (pinfunction "A_1") (pintype "passive"))
      (node (ref "R43") (pin "1") (pinfunction "1_1") (pintype "passive"))
    )
    (net (code "115") (name "Net-(LED33-A)") (class "Default")
      (node (ref "LED33") (pin "1") (pinfunction "A_1") (pintype "passive"))
      (node (ref "R44") (pin "1") (pinfunction "1_1") (pintype "passive"))
    )
    (net (code "116") (name "Net-(LED34-A)") (class "Default")
      (node (ref "LED34") (pin "1") (pinfunction "A_1") (pintype "passive"))
      (node (ref "R45") (pin "1") (pinfunction "1_1") (pintype "passive"))
    )
    (net (code "117") (name "Net-(LED35-A)") (class "Default")
      (node (ref "LED35") (pin "1") (pinfunction "A_1") (pintype "passive"))
      (node (ref "R46") (pin "1") (pinfunction "1_1") (pintype "passive"))
    )
    (net (code "118") (name "Net-(LED36-A)") (class "Default")
      (node (ref "LED36") (pin "1") (pinfunction "A_1") (pintype "passive"))
      (node (ref "R47") (pin "1") (pinfunction "1_1") (pintype "passive"))
    )
    (net (code "119") (name "Net-(LED37-A)") (class "Default")
      (node (ref "LED37") (pin "1") (pinfunction "A_1") (pintype "passive"))
      (node (ref "R48") (pin "1") (pinfunction "1_1") (pintype "passive"))
    )
    (net (code "120") (name "Net-(LED38-A)") (class "Default")
      (node (ref "LED38") (pin "1") (pinfunction "A_1") (pintype "passive"))
      (node (ref "R49") (pin "1") (pinfunction "1_1") (pintype "passive"))
    )
    (net (code "121") (name "Net-(LED39-A)") (class "Default")
      (node (ref "LED39") (pin "1") (pinfunction "A_1") (pintype "passive"))
      (node (ref "R50") (pin "1") (pinfunction "1_1") (pintype "passive"))
    )
    (net (code "122") (name "Net-(LED40-A)") (class "Default")
      (node (ref "LED40") (pin "1") (pinfunction "A_1") (pintype "passive"))
      (node (ref "R51") (pin "1") (pinfunction "1_1") (pintype "passive"))
    )
    (net (code "123") (name "Net-(LED41-A)") (class "Default")
      (node (ref "LED41") (pin "1") (pinfunction "A_1") (pintype "passive"))
      (node (ref "R52") (pin "1") (pinfunction "1_1") (pintype "passive"))
    )
    (net (code "124") (name "Net-(LED42-A)") (class "Default")
      (node (ref "LED42") (pin "1") (pinfunction "A_1") (pintype "passive"))
      (node (ref "R53") (pin "1") (pinfunction "1_1") (pintype "passive"))
    )
    (net (code "125") (name "Net-(LED43-A)") (class "Default")
      (node (ref "LED43") (pin "1") (pinfunction "A_1") (pintype "passive"))
      (node (ref "R54") (pin "1") (pinfunction "1_1") (pintype "passive"))
    )
    (net (code "126") (name "Net-(LED44-A)") (class "Default")
      (node (ref "LED44") (pin "1") (pinfunction "A_1") (pintype "passive"))
      (node (ref "R55") (pin "1") (pinfunction "1_1") (pintype "passive"))
    )
    (net (code "127") (name "Net-(LED46-A)") (class "Default")
      (node (ref "LED46") (pin "1") (pinfunction "A_1") (pintype "passive"))
      (node (ref "R57") (pin "1") (pinfunction "1_1") (pintype "passive"))
    )
    (net (code "128") (name "Net-(LED47-A)") (class "Default")
      (node (ref "LED47") (pin "1") (pinfunction "A_1") (pintype "passive"))
      (node (ref "R58") (pin "1") (pinfunction "1_1") (pintype "passive"))
    )
    (net (code "129") (name "Net-(LED48-A)") (class "Default")
      (node (ref "LED48") (pin "1") (pinfunction "A_1") (pintype "passive"))
      (node (ref "R59") (pin "1") (pinfunction "1_1") (pintype "passive"))
    )
    (net (code "130") (name "Net-(LED49-A)") (class "Default")
      (node (ref "LED49") (pin "1") (pinfunction "A_1") (pintype "passive"))
      (node (ref "R60") (pin "1") (pinfunction "1_1") (pintype "passive"))
    )
    (net (code "131") (name "Net-(LED50-A)") (class "Default")
      (node (ref "LED50") (pin "1") (pinfunction "A_1") (pintype "passive"))
      (node (ref "R61") (pin "1") (pinfunction "1_1") (pintype "passive"))
    )
    (net (code "132") (name "Net-(LED51-A)") (class "Default")
      (node (ref "LED51") (pin "1") (pinfunction "A_1") (pintype "passive"))
      (node (ref "R62") (pin "1") (pinfunction "1_1") (pintype "passive"))
    )
    (net (code "133") (name "Net-(LED52-A)") (class "Default")
      (node (ref "LED52") (pin "1") (pinfunction "A_1") (pintype "passive"))
      (node (ref "R63") (pin "1") (pinfunction "1_1") (pintype "passive"))
    )
    (net (code "134") (name "Net-(Q1-G)") (class "Default")
      (node (ref "Q1") (pin "1") (pinfunction "G_1") (pintype "passive"))
      (node (ref "Q7") (pin "3") (pinfunction "D_3") (pintype "passive"))
      (node (ref "R3") (pin "2") (pinfunction "2_2") (pintype "passive"))
    )
    (net (code "135") (name "Net-(Q2-D)") (class "Default")
      (node (ref "Q2") (pin "3") (pinfunction "D_3") (pintype "passive"))
      (node (ref "Q5") (pin "3") (pinfunction "D_3") (pintype "passive"))
    )
    (net (code "136") (name "Net-(U1A-OUT_ANT)") (class "Default")
      (node (ref "U1") (pin "20") (pinfunction "OUT_ANT_20") (pintype "bidirectional"))
      (node (ref "U1") (pin "22") (pinfunction "OUT_MOD_22") (pintype "bidirectional"))
    )
    (net (code "137") (name "V_BATT") (class "Default")
      (node (ref "IC2") (pin "3") (pinfunction "BAT_3") (pintype "bidirectional"))
      (node (ref "J1") (pin "1") (pinfunction "NO_1") (pintype "bidirectional"))
      (node (ref "J4") (pin "1") (pinfunction "1_1") (pintype "passive"))
      (node (ref "Q2") (pin "2") (pinfunction "S_2") (pintype "passive"))
      (node (ref "R15") (pin "2") (pinfunction "2_2") (pintype "passive"))
      (node (ref "R19") (pin "1") (pinfunction "1_1") (pintype "passive"))
    )
    (net (code "138") (name "V_USB") (class "Default")
      (node (ref "C4") (pin "1") (pinfunction "1_1") (pintype "passive"))
      (node (ref "D63") (pin "2") (pinfunction "A_2") (pintype "bidirectional"))
      (node (ref "D67") (pin "A") (pinfunction "A_A") (pintype "passive"))
      (node (ref "FUSE") (pin "1") (pinfunction "1_1") (pintype "passive"))
      (node (ref "IC2") (pin "4") (pinfunction "VCC_4") (pintype "bidirectional"))
      (node (ref "LED2") (pin "A") (pinfunction "A_A") (pintype "passive"))
      (node (ref "PROG1") (pin "6") (pinfunction "6_6") (pintype "passive"))
      (node (ref "Q5") (pin "1") (pinfunction "G_1") (pintype "passive"))
      (node (ref "R17") (pin "2") (pinfunction "2_2") (pintype "passive"))
      (node (ref "U1") (pin "12") (pinfunction "VBUS_12") (pintype "power_in"))
    )
    (net (code "139") (name "unconnected-(J1-NC-Pad3)") (class "Default")
      (node (ref "J1") (pin "3") (pinfunction "NC_3") (pintype "no_connect"))
    )
    (net (code "140") (name "unconnected-(U1A-P0.07-Pad33)") (class "Default")
      (node (ref "U1") (pin "33") (pinfunction "P0.07_33") (pintype "bidirectional"))
    )
    (net (code "141") (name "unconnected-(U1A-P0.14-Pad5)") (class "Default")
      (node (ref "U1") (pin "5") (pinfunction "P0.14_5") (pintype "bidirectional"))
    )
    (net (code "142") (name "unconnected-(U1A-P0.17-Pad27)") (class "Default")
      (node (ref "U1") (pin "27") (pinfunction "P0.17_27") (pintype "bidirectional"))
    )
    (net (code "143") (name "unconnected-(U1A-P0.20-Pad15)") (class "Default")
      (node (ref "U1") (pin "15") (pinfunction "P0.20_15") (pintype "bidirectional"))
    )
    (net (code "144") (name "unconnected-(U1A-P0.21-Pad11)") (class "Default")
      (node (ref "U1") (pin "11") (pinfunction "P0.21_11") (pintype "bidirectional"))
    )
    (net (code "145") (name "unconnected-(U1A-P0.22-Pad17)") (class "Default")
      (node (ref "U1") (pin "17") (pinfunction "P0.22_17") (pintype "bidirectional"))
    )
    (net (code "146") (name "unconnected-(U1A-P0.25-Pad41)") (class "Default")
      (node (ref "U1") (pin "41") (pinfunction "P0.25_41") (pintype "bidirectional"))
    )
    (net (code "147") (name "unconnected-(U1A-P0.27-Pad39)") (class "Default")
      (node (ref "U1") (pin "39") (pinfunction "P0.27_39") (pintype "bidirectional"))
    )
    (net (code "148") (name "unconnected-(U1A-P1.00-Pad57)") (class "Default")
      (node (ref "U1") (pin "57") (pinfunction "P1.00_57") (pintype "bidirectional"))
    )
    (net (code "149") (name "unconnected-(U1A-P1.01-Pad64)") (class "Default")
      (node (ref "U1") (pin "64") (pinfunction "P1.01_64") (pintype "bidirectional"))
    )
    (net (code "150") (name "unconnected-(U1A-P1.02-Pad49)") (class "Default")
      (node (ref "U1") (pin "49") (pinfunction "P1.02_49") (pintype "bidirectional"))
    )
    (net (code "151") (name "unconnected-(U1A-P1.03-Pad58)") (class "Default")
      (node (ref "U1") (pin "58") (pinfunction "P1.03_58") (pintype "bidirectional"))
    )
    (net (code "152") (name "unconnected-(U1A-P1.04-Pad63)") (class "Default")
      (node (ref "U1") (pin "63") (pinfunction "P1.04_63") (pintype "bidirectional"))
    )
    (net (code "153") (name "unconnected-(U1A-P1.05-Pad54)") (class "Default")
      (node (ref "U1") (pin "54") (pinfunction "P1.05_54") (pintype "bidirectional"))
    )
    (net (code "154") (name "unconnected-(U1A-P1.06-Pad50)") (class "Default")
      (node (ref "U1") (pin "50") (pinfunction "P1.06_50") (pintype "bidirectional"))
    )
    (net (code "155") (name "unconnected-(U1A-P1.07-Pad62)") (class "Default")
      (node (ref "U1") (pin "62") (pinfunction "P1.07_62") (pintype "bidirectional"))
    )
    (net (code "156") (name "unconnected-(U1A-P1.09-Pad56)") (class "Default")
      (node (ref "U1") (pin "56") (pinfunction "P1.09_56") (pintype "bidirectional"))
    )
    (net (code "157") (name "unconnected-(U1A-P1.10-Pad60)") (class "Default")
      (node (ref "U1") (pin "60") (pinfunction "P1.10_60") (pintype "bidirectional"))
    )
    (net (code "158") (name "unconnected-(U1A-P1.11-Pad61)") (class "Default")
      (node (ref "U1") (pin "61") (pinfunction "P1.11_61") (pintype "bidirectional"))
    )
    (net (code "159") (name "unconnected-(U1A-P1.12-Pad59)") (class "Default")
      (node (ref "U1") (pin "59") (pinfunction "P1.12_59") (pintype "bidirectional"))
    )
    (net (code "160") (name "unconnected-(U1A-P1.13-Pad53)") (class "Default")
      (node (ref "U1") (pin "53") (pinfunction "P1.13_53") (pintype "bidirectional"))
    )
    (net (code "161") (name "unconnected-(U1A-P1.14-Pad52)") (class "Default")
      (node (ref "U1") (pin "52") (pinfunction "P1.14_52") (pintype "bidirectional"))
    )
    (net (code "162") (name "unconnected-(U1A-P1.15-Pad51)") (class "Default")
      (node (ref "U1") (pin "51") (pinfunction "P1.15_51") (pintype "bidirectional"))
    )
    (net (code "163") (name "unconnected-(U1B-NC-Pad65)") (class "Default")
      (node (ref "U1") (pin "65") (pinfunction "NC_65") (pintype "passive"))
    )
    (net (code "164") (name "unconnected-(U1B-NC-Pad66)") (class "Default")
      (node (ref "U1") (pin "66") (pinfunction "NC_66") (pintype "passive"))
    )
    (net (code "165") (name "unconnected-(U1B-NC-Pad67)") (class "Default")
      (node (ref "U1") (pin "67") (pinfunction "NC_67") (pintype "passive"))
    )
    (net (code "166") (name "unconnected-(U1B-NC-Pad68)") (class "Default")
      (node (ref "U1") (pin "68") (pinfunction "NC_68") (pintype "passive"))
    )
    (net (code "167") (name "unconnected-(U1B-NC-Pad69)") (class "Default")
      (node (ref "U1") (pin "69") (pinfunction "NC_69") (pintype "passive"))
    )
    (net (code "168") (name "unconnected-(U1B-NC-Pad70)") (class "Default")
      (node (ref "U1") (pin "70") (pinfunction "NC_70") (pintype "passive"))
    )
    (net (code "169") (name "unconnected-(U1B-NC-Pad71)") (class "Default")
      (node (ref "U1") (pin "71") (pinfunction "NC_71") (pintype "passive"))
    )
    (net (code "170") (name "unconnected-(U1B-NC-Pad72)") (class "Default")
      (node (ref "U1") (pin "72") (pinfunction "NC_72") (pintype "passive"))
    )
    (net (code "171") (name "unconnected-(U1B-NC-Pad73)") (class "Default")
      (node (ref "U1") (pin "73") (pinfunction "NC_73") (pintype "passive"))
    )
    (net (code "172") (name "unconnected-(U1B-NC-Pad74)") (class "Default")
      (node (ref "U1") (pin "74") (pinfunction "NC_74") (pintype "passive"))
    )
    (net (code "173") (name "unconnected-(U1B-NC-Pad75)") (class "Default")
      (node (ref "U1") (pin "75") (pinfunction "NC_75") (pintype "passive"))
    )
    (net (code "174") (name "unconnected-(U1B-NC-Pad76)") (class "Default")
      (node (ref "U1") (pin "76") (pinfunction "NC_76") (pintype "passive"))
    )
    (net (code "175") (name "unconnected-(U1B-NC-Pad77)") (class "Default")
      (node (ref "U1") (pin "77") (pinfunction "NC_77") (pintype "passive"))
    )
    (net (code "176") (name "unconnected-(U1B-NC-Pad78)") (class "Default")
      (node (ref "U1") (pin "78") (pinfunction "NC_78") (pintype "passive"))
    )
  )
)
